# schematic-final.net
KiCad netlist of a schematic drawn in EAGLE
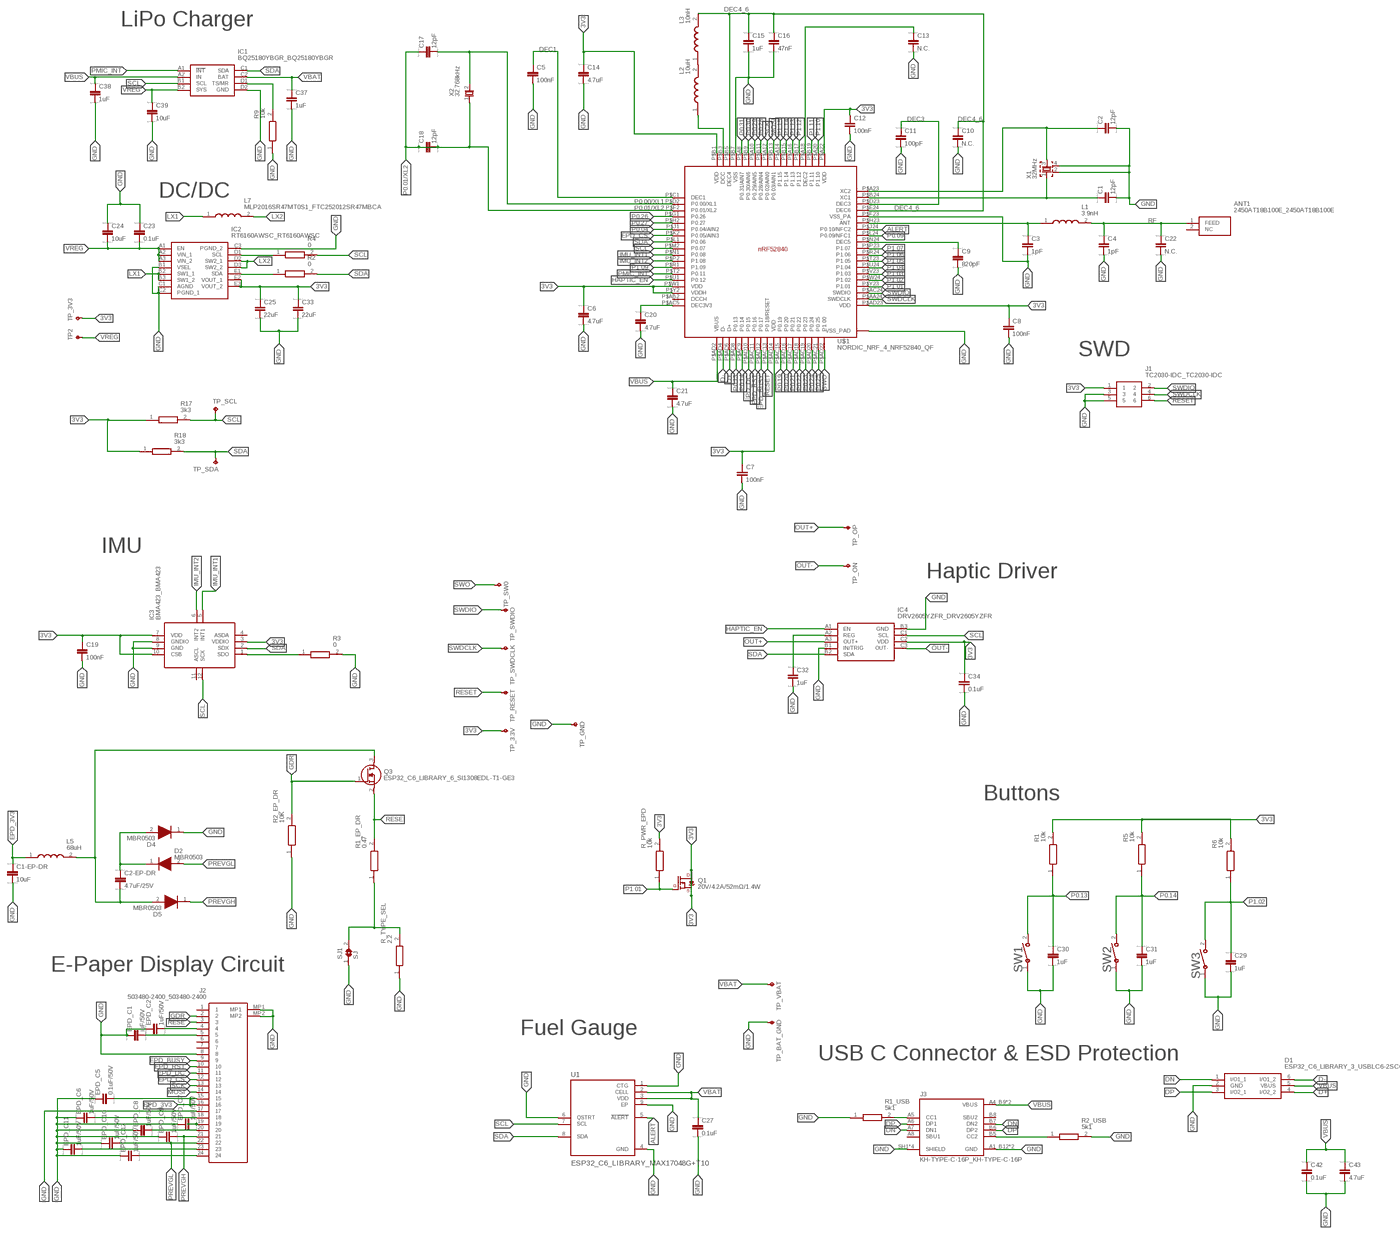
[diagram p0: schematic, sheet 1, overview]
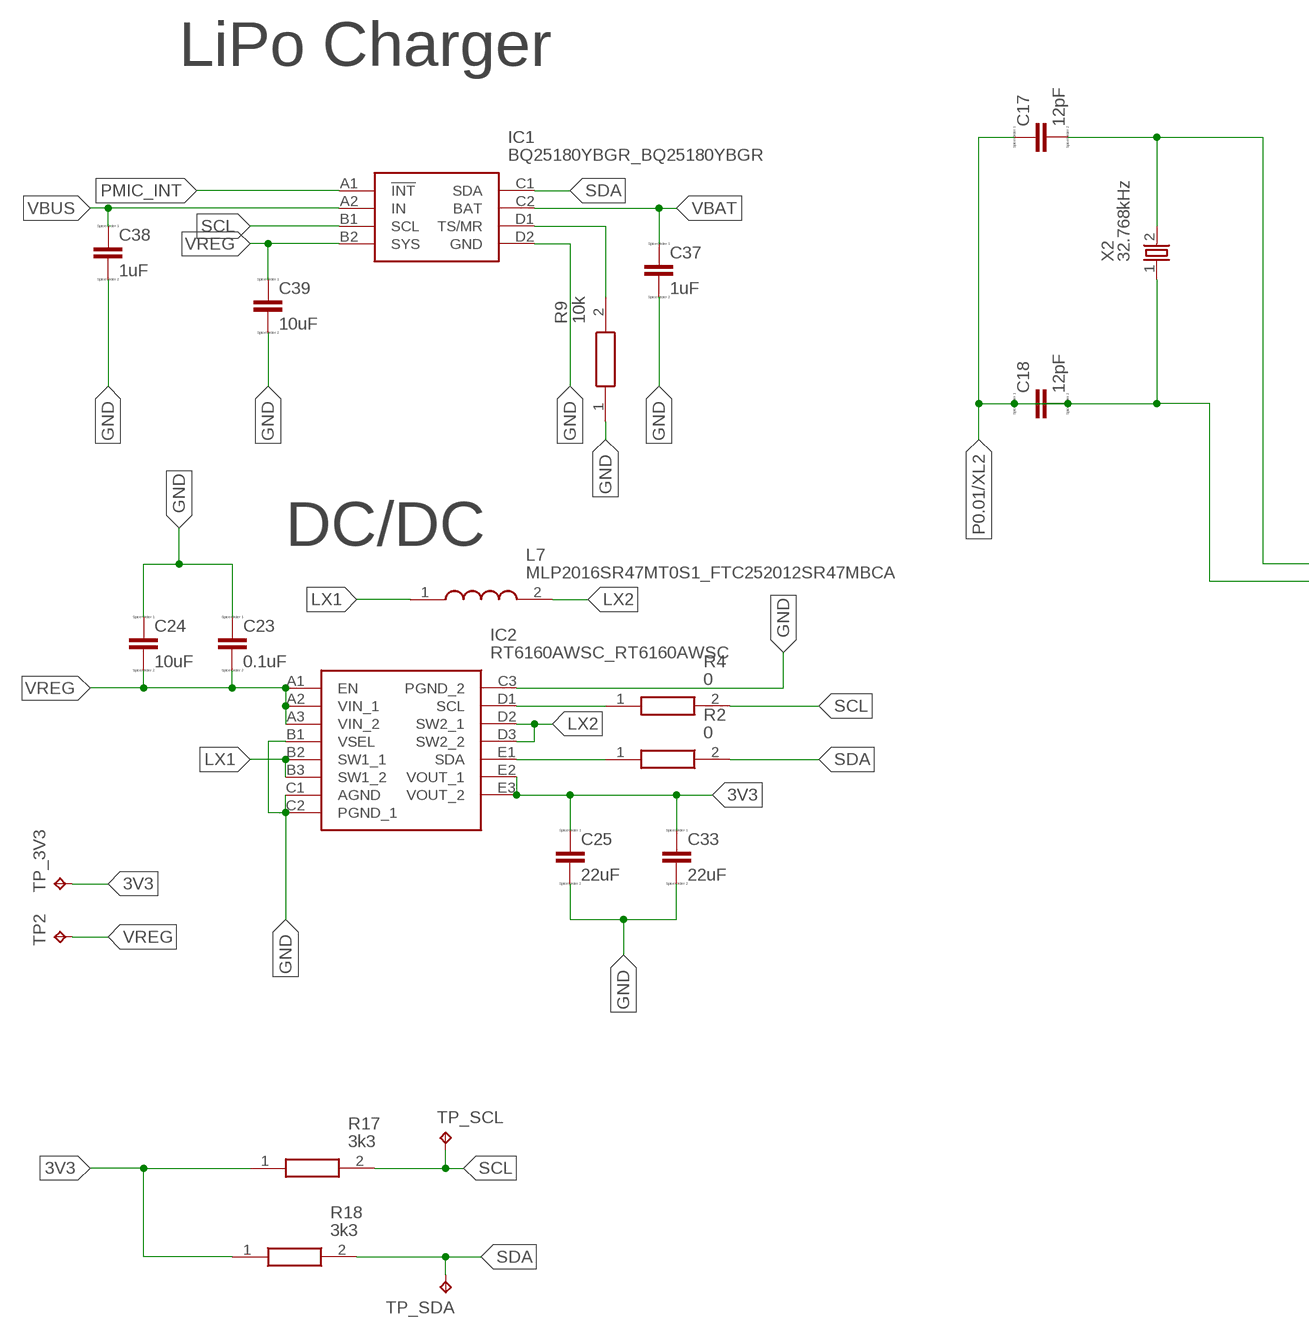
[diagram p1: schematic, sheet 1, part 1 of 4]
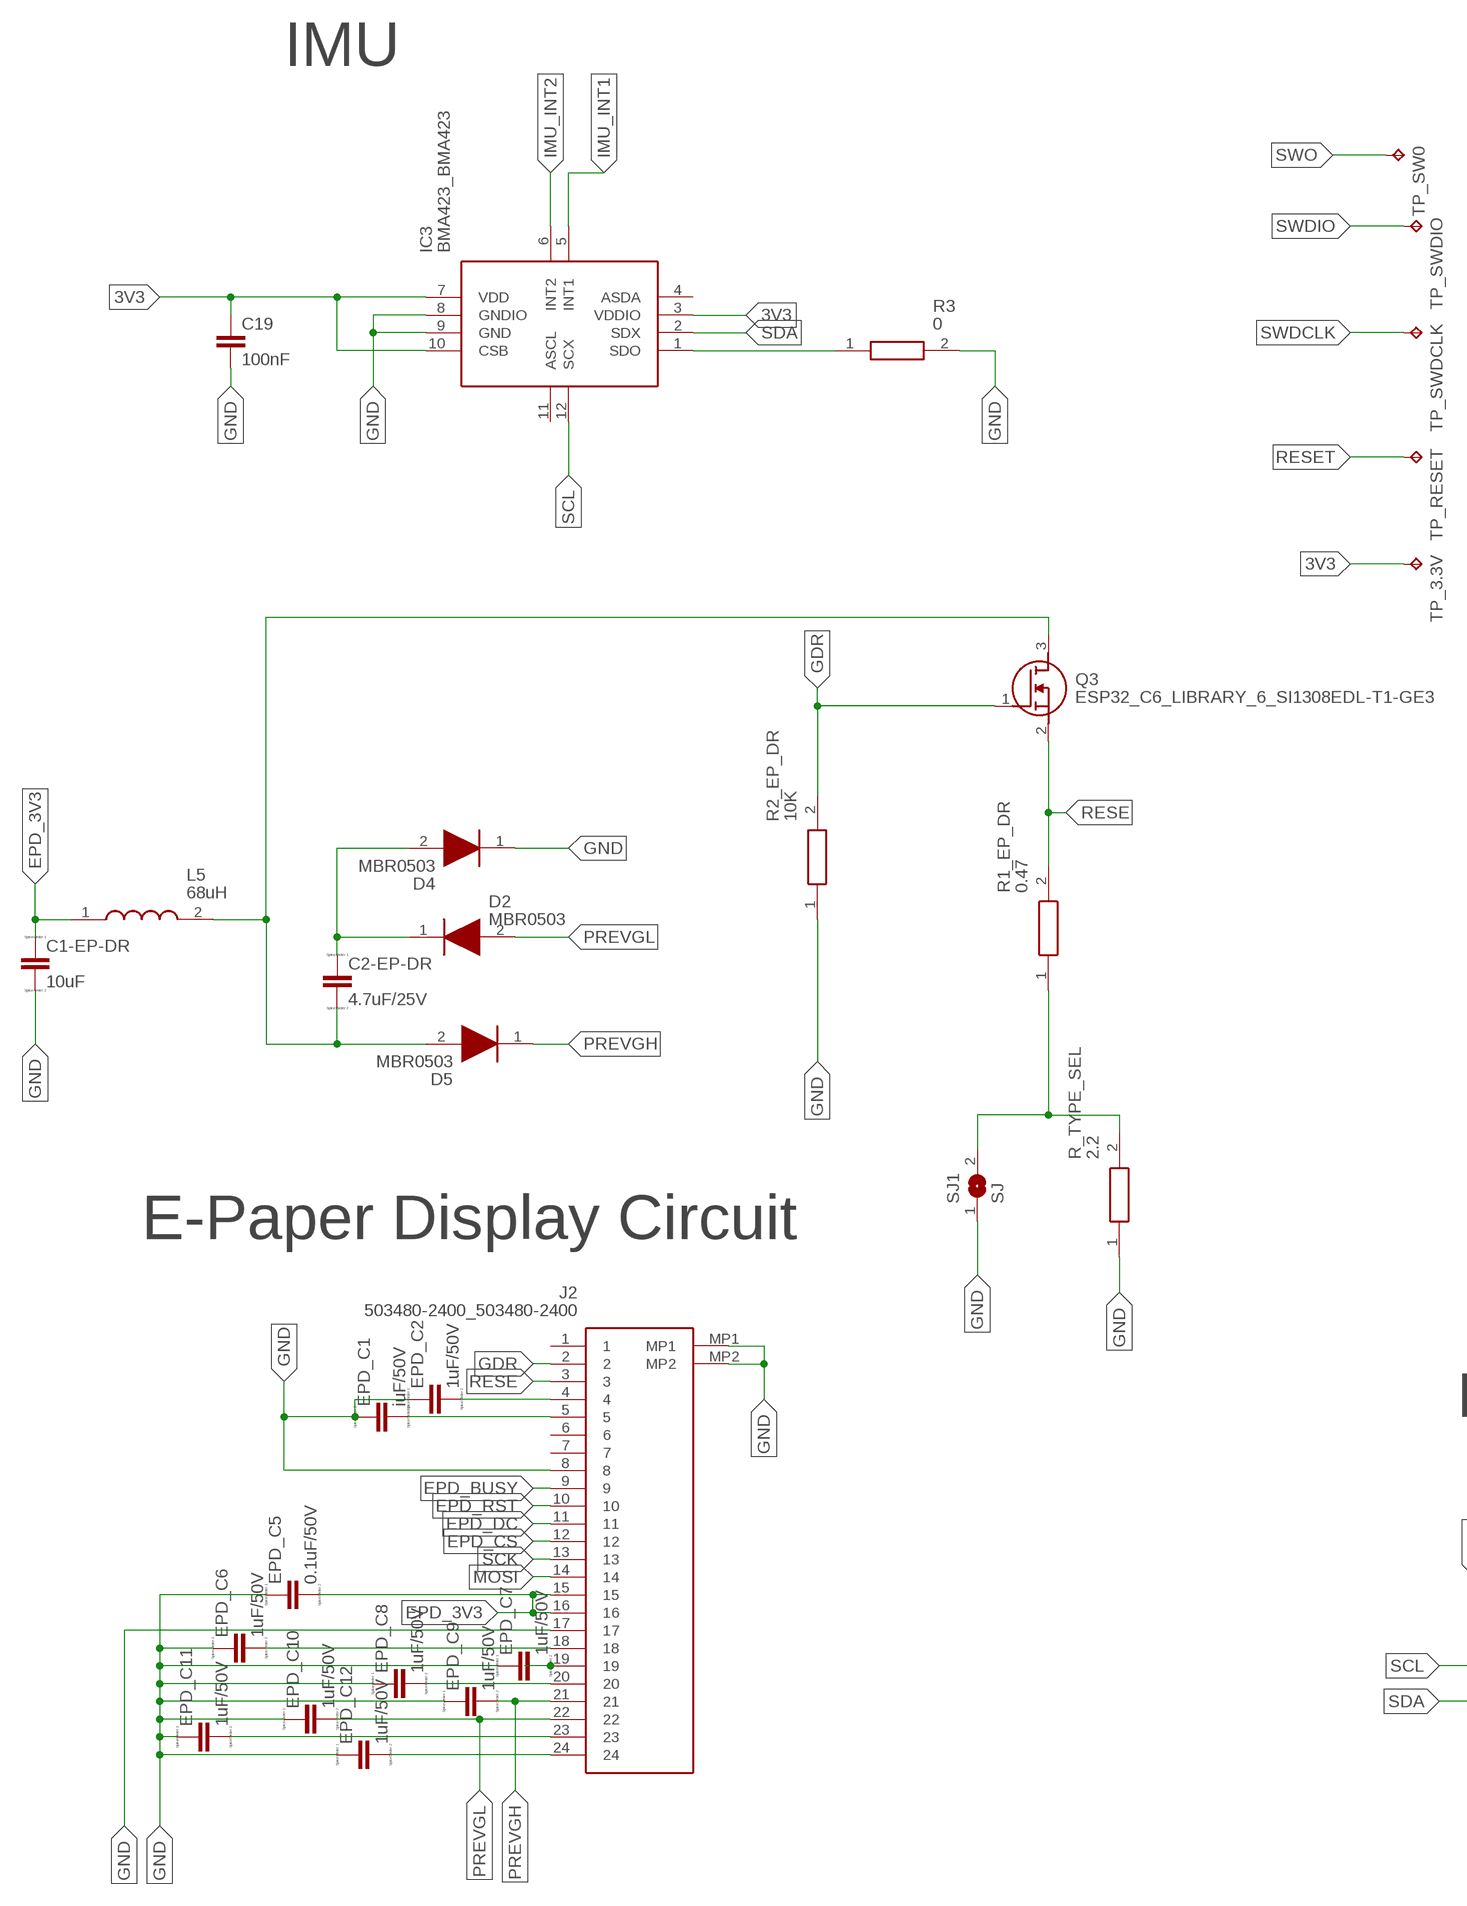
[diagram p2: schematic, sheet 1, part 2 of 4]
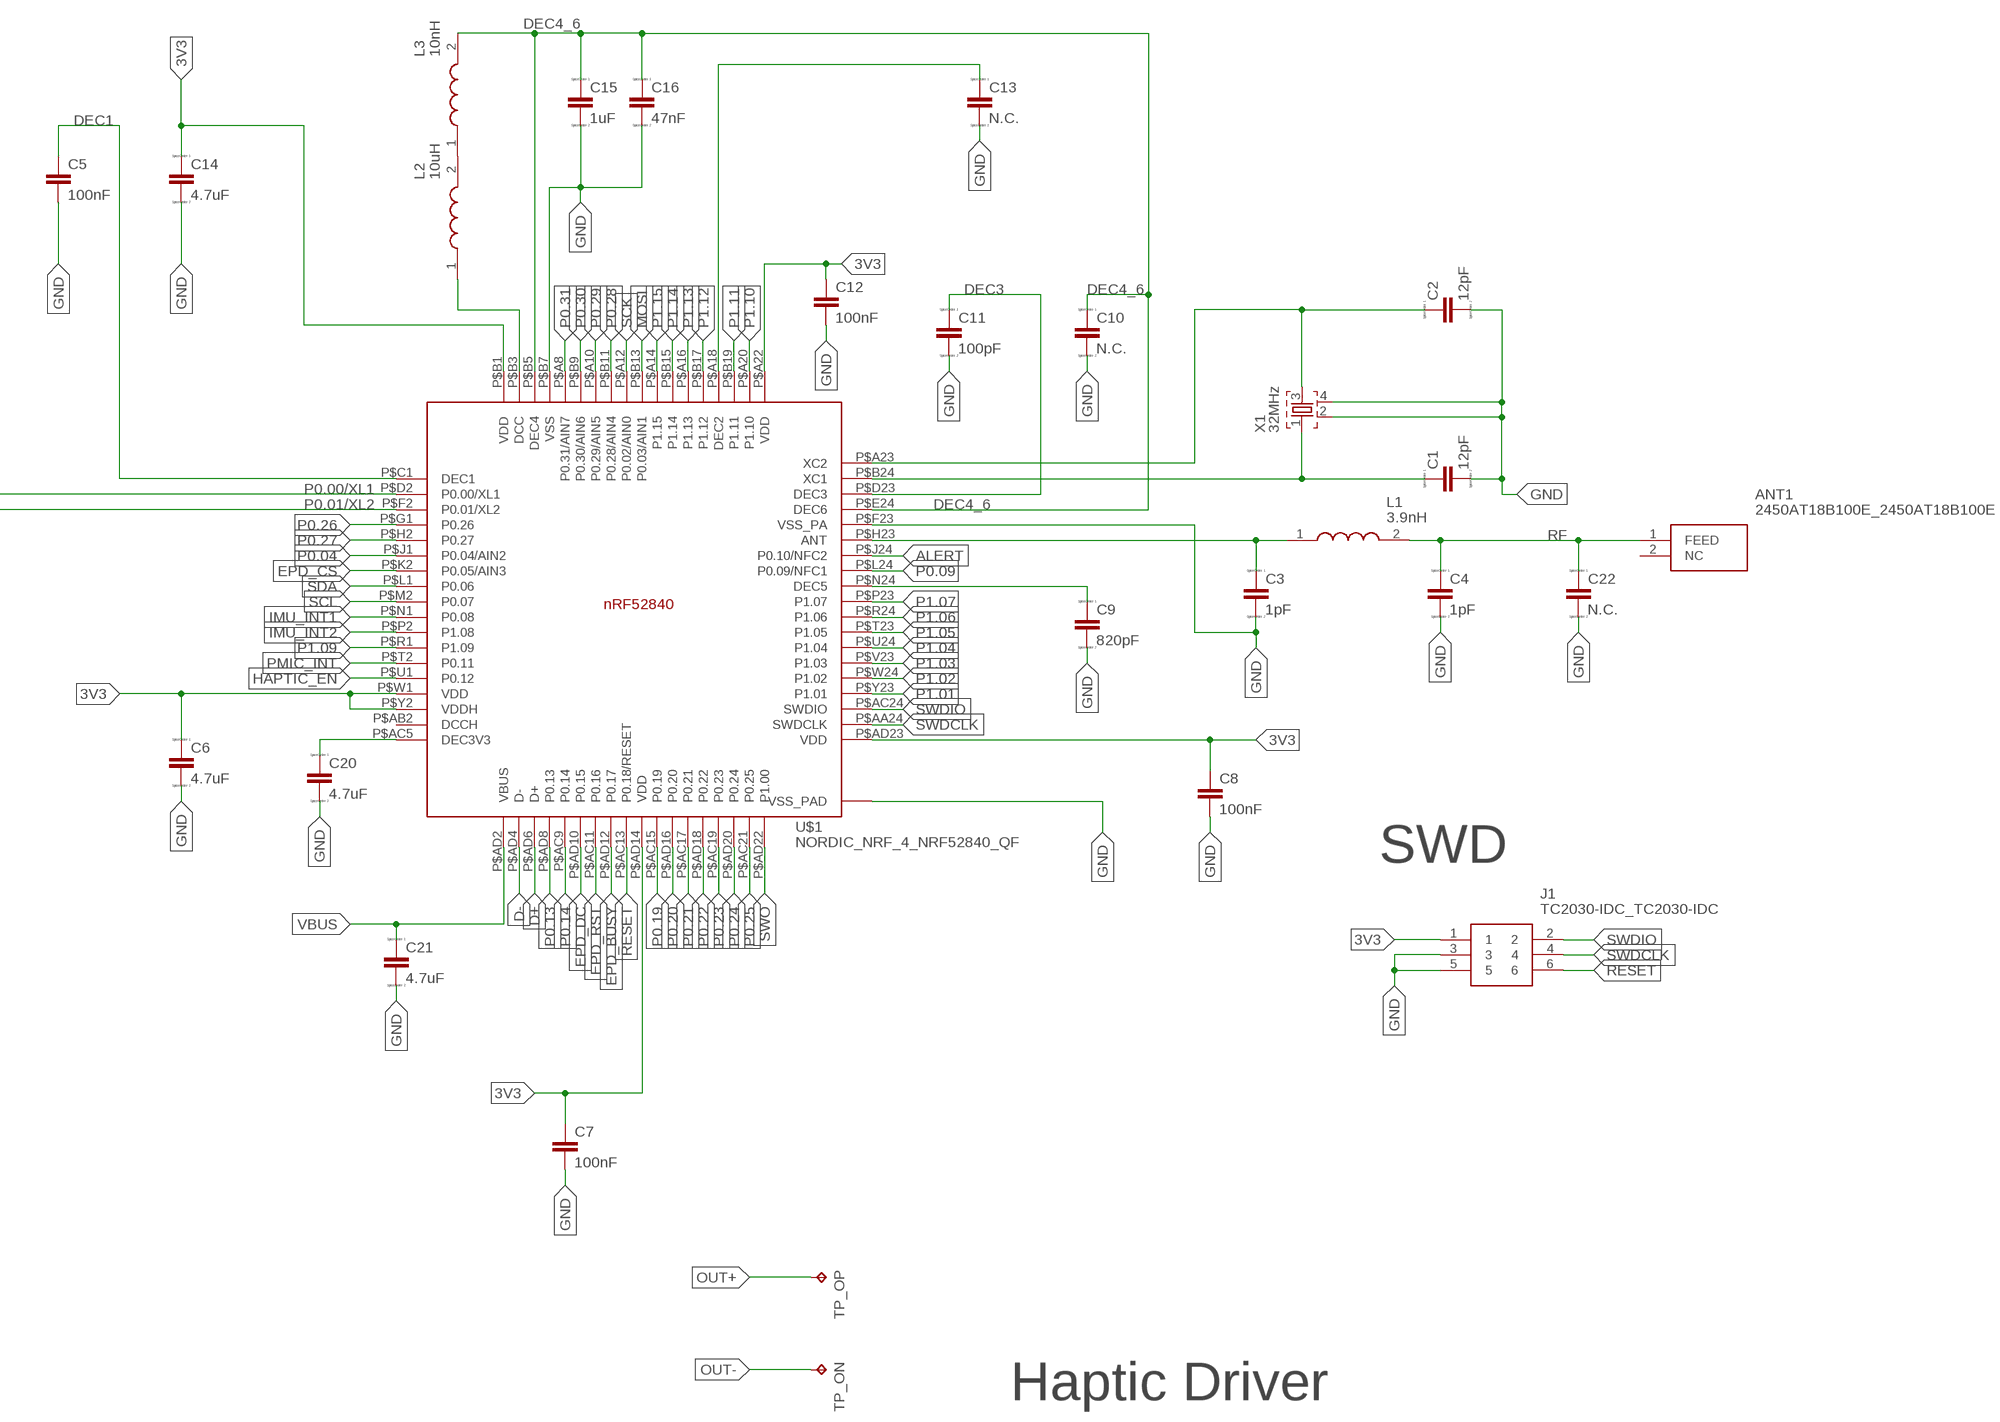
[diagram p3: schematic, sheet 1, part 3 of 4]
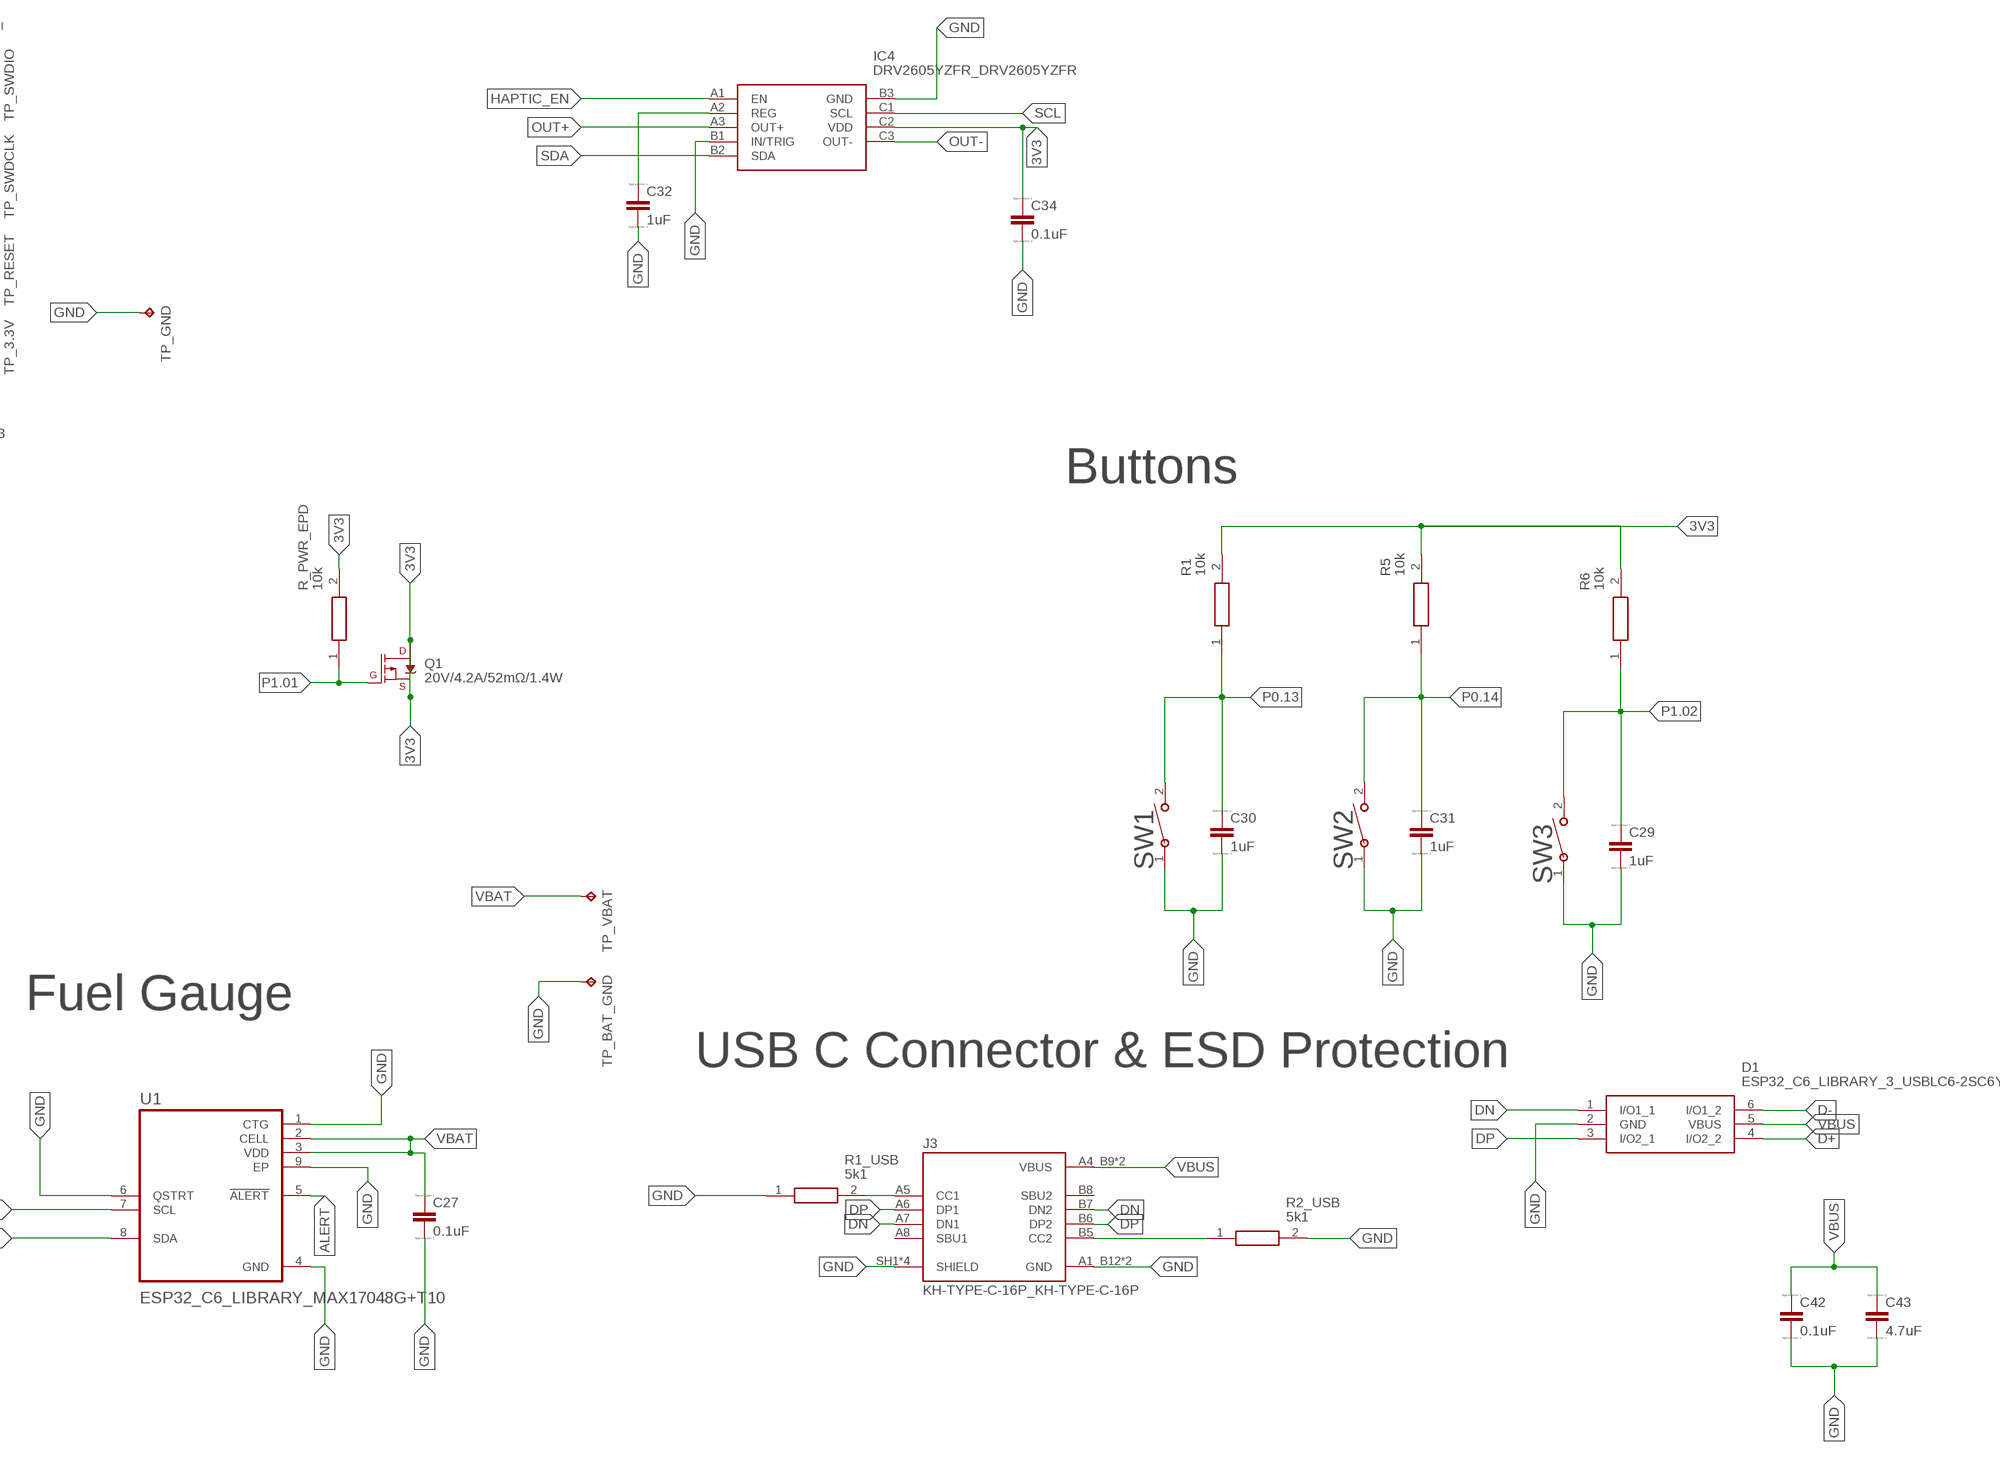
[diagram p4: schematic, sheet 1, part 4 of 4]

(export (version "E")
  (design (tool "Eeschema 10.0.6"))
  (components
    (comp (ref "ANT1")
      (value "2450AT18B100E_2450AT18B100E")
      (footprint "eagle-import:2450AT18B100E_ANTC3216X140N")
      (fields
        (field (name "ARROW_PART_NUMBER") "2450AT18B100E")
        (field (name "MOUSER_PART_NUMBER") "609-2450AT18B100E")
      )
      (libsource (lib "eagle-import") (part "2450AT18B100E_2450AT18B100E"))
    )
    (comp (ref "C1")
      (value "12pF")
      (footprint "eagle-import:ESP32_C6_LIBRARY_1_ESP32_WROVER_EAGLE-LTSPICE_C0402")
      (libsource (lib "eagle-import") (part "ESP32_C6_LIBRARY_1_ESP32_WROVER_EAGLE-LTSPICE_CC0402"))
    )
    (comp (ref "C1-EP-DR")
      (value "10uF")
      (footprint "eagle-import:ESP32_C6_LIBRARY_1_ESP32_WROVER_EAGLE-LTSPICE_C0402")
      (libsource (lib "eagle-import") (part "ESP32_C6_LIBRARY_1_ESP32_WROVER_EAGLE-LTSPICE_CC0402"))
    )
    (comp (ref "C2")
      (value "12pF")
      (footprint "eagle-import:ESP32_C6_LIBRARY_1_ESP32_WROVER_EAGLE-LTSPICE_C0402")
      (libsource (lib "eagle-import") (part "ESP32_C6_LIBRARY_1_ESP32_WROVER_EAGLE-LTSPICE_CC0402"))
    )
    (comp (ref "C2-EP-DR")
      (value "4.7uF/25V")
      (footprint "eagle-import:ESP32_C6_LIBRARY_1_ESP32_WROVER_EAGLE-LTSPICE_C0402")
      (libsource (lib "eagle-import") (part "ESP32_C6_LIBRARY_1_ESP32_WROVER_EAGLE-LTSPICE_CC0402"))
    )
    (comp (ref "C3")
      (value "1pF")
      (footprint "eagle-import:ESP32_C6_LIBRARY_1_ESP32_WROVER_EAGLE-LTSPICE_C0402")
      (libsource (lib "eagle-import") (part "ESP32_C6_LIBRARY_1_ESP32_WROVER_EAGLE-LTSPICE_CC0402"))
    )
    (comp (ref "C4")
      (value "1pF")
      (footprint "eagle-import:ESP32_C6_LIBRARY_1_ESP32_WROVER_EAGLE-LTSPICE_C0402")
      (libsource (lib "eagle-import") (part "ESP32_C6_LIBRARY_1_ESP32_WROVER_EAGLE-LTSPICE_CC0402"))
    )
    (comp (ref "C5")
      (value "100nF")
      (footprint "eagle-import:NORDIC_NRF_3_RESC0201_L")
      (libsource (lib "eagle-import") (part "NORDIC_NRF_3_CAPACITOR_0201_L"))
    )
    (comp (ref "C6")
      (value "4.7uF")
      (footprint "eagle-import:ESP32_C6_LIBRARY_1_ESP32_WROVER_EAGLE-LTSPICE_C0402")
      (libsource (lib "eagle-import") (part "ESP32_C6_LIBRARY_1_ESP32_WROVER_EAGLE-LTSPICE_CC0402"))
    )
    (comp (ref "C7")
      (value "100nF")
      (footprint "eagle-import:NORDIC_NRF_3_RESC0201_L")
      (libsource (lib "eagle-import") (part "NORDIC_NRF_3_CAPACITOR_0201_L"))
    )
    (comp (ref "C8")
      (value "100nF")
      (footprint "eagle-import:NORDIC_NRF_3_RESC0201_L")
      (libsource (lib "eagle-import") (part "NORDIC_NRF_3_CAPACITOR_0201_L"))
    )
    (comp (ref "C9")
      (value "820pF")
      (footprint "eagle-import:ESP32_C6_LIBRARY_1_ESP32_WROVER_EAGLE-LTSPICE_C0402")
      (libsource (lib "eagle-import") (part "ESP32_C6_LIBRARY_1_ESP32_WROVER_EAGLE-LTSPICE_CC0402"))
    )
    (comp (ref "C10")
      (value "N.C.")
      (footprint "eagle-import:ESP32_C6_LIBRARY_1_ESP32_WROVER_EAGLE-LTSPICE_C0402")
      (libsource (lib "eagle-import") (part "ESP32_C6_LIBRARY_1_ESP32_WROVER_EAGLE-LTSPICE_CC0402"))
    )
    (comp (ref "C11")
      (value "100pF")
      (footprint "eagle-import:ESP32_C6_LIBRARY_1_ESP32_WROVER_EAGLE-LTSPICE_C0402")
      (libsource (lib "eagle-import") (part "ESP32_C6_LIBRARY_1_ESP32_WROVER_EAGLE-LTSPICE_CC0402"))
    )
    (comp (ref "C12")
      (value "100nF")
      (footprint "eagle-import:NORDIC_NRF_3_RESC0201_L")
      (libsource (lib "eagle-import") (part "NORDIC_NRF_3_CAPACITOR_0201_L"))
    )
    (comp (ref "C13")
      (value "N.C.")
      (footprint "eagle-import:ESP32_C6_LIBRARY_1_ESP32_WROVER_EAGLE-LTSPICE_C0402")
      (libsource (lib "eagle-import") (part "ESP32_C6_LIBRARY_1_ESP32_WROVER_EAGLE-LTSPICE_CC0402"))
    )
    (comp (ref "C14")
      (value "4.7uF")
      (footprint "eagle-import:ESP32_C6_LIBRARY_1_ESP32_WROVER_EAGLE-LTSPICE_C0402")
      (libsource (lib "eagle-import") (part "ESP32_C6_LIBRARY_1_ESP32_WROVER_EAGLE-LTSPICE_CC0402"))
    )
    (comp (ref "C15")
      (value "1uF")
      (footprint "eagle-import:ESP32_C6_LIBRARY_1_ESP32_WROVER_EAGLE-LTSPICE_C0402")
      (libsource (lib "eagle-import") (part "ESP32_C6_LIBRARY_1_ESP32_WROVER_EAGLE-LTSPICE_CC0402"))
    )
    (comp (ref "C16")
      (value "47nF")
      (footprint "eagle-import:ESP32_C6_LIBRARY_1_ESP32_WROVER_EAGLE-LTSPICE_C0402")
      (libsource (lib "eagle-import") (part "ESP32_C6_LIBRARY_1_ESP32_WROVER_EAGLE-LTSPICE_CC0402"))
    )
    (comp (ref "C17")
      (value "12pF")
      (footprint "eagle-import:ESP32_C6_LIBRARY_1_ESP32_WROVER_EAGLE-LTSPICE_C0402")
      (libsource (lib "eagle-import") (part "ESP32_C6_LIBRARY_1_ESP32_WROVER_EAGLE-LTSPICE_CC0402"))
    )
    (comp (ref "C18")
      (value "12pF")
      (footprint "eagle-import:ESP32_C6_LIBRARY_1_ESP32_WROVER_EAGLE-LTSPICE_C0402")
      (libsource (lib "eagle-import") (part "ESP32_C6_LIBRARY_1_ESP32_WROVER_EAGLE-LTSPICE_CC0402"))
    )
    (comp (ref "C19")
      (value "100nF")
      (footprint "eagle-import:NORDIC_NRF_3_RESC0201_L")
      (libsource (lib "eagle-import") (part "NORDIC_NRF_3_CAPACITOR_0201_L"))
    )
    (comp (ref "C20")
      (value "4.7uF")
      (footprint "eagle-import:ESP32_C6_LIBRARY_1_ESP32_WROVER_EAGLE-LTSPICE_C0402")
      (libsource (lib "eagle-import") (part "ESP32_C6_LIBRARY_1_ESP32_WROVER_EAGLE-LTSPICE_CC0402"))
    )
    (comp (ref "C21")
      (value "4.7uF")
      (footprint "eagle-import:ESP32_C6_LIBRARY_1_ESP32_WROVER_EAGLE-LTSPICE_C0402")
      (libsource (lib "eagle-import") (part "ESP32_C6_LIBRARY_1_ESP32_WROVER_EAGLE-LTSPICE_CC0402"))
    )
    (comp (ref "C22")
      (value "N.C.")
      (footprint "eagle-import:ESP32_C6_LIBRARY_1_ESP32_WROVER_EAGLE-LTSPICE_C0402")
      (libsource (lib "eagle-import") (part "ESP32_C6_LIBRARY_1_ESP32_WROVER_EAGLE-LTSPICE_CC0402"))
    )
    (comp (ref "C23")
      (value "0.1uF")
      (footprint "eagle-import:ESP32_C6_LIBRARY_1_ESP32_WROVER_EAGLE-LTSPICE_C0402")
      (libsource (lib "eagle-import") (part "ESP32_C6_LIBRARY_1_ESP32_WROVER_EAGLE-LTSPICE_CC0402"))
    )
    (comp (ref "C24")
      (value "10uF")
      (footprint "eagle-import:ESP32_C6_LIBRARY_1_ESP32_WROVER_EAGLE-LTSPICE_C0402")
      (libsource (lib "eagle-import") (part "ESP32_C6_LIBRARY_1_ESP32_WROVER_EAGLE-LTSPICE_CC0402"))
    )
    (comp (ref "C25")
      (value "22uF")
      (footprint "eagle-import:ESP32_C6_LIBRARY_1_ESP32_WROVER_EAGLE-LTSPICE_C0402")
      (libsource (lib "eagle-import") (part "ESP32_C6_LIBRARY_1_ESP32_WROVER_EAGLE-LTSPICE_CC0402"))
    )
    (comp (ref "C27")
      (value "0.1uF")
      (footprint "eagle-import:ESP32_C6_LIBRARY_1_ESP32_WROVER_EAGLE-LTSPICE_C0402")
      (libsource (lib "eagle-import") (part "ESP32_C6_LIBRARY_1_ESP32_WROVER_EAGLE-LTSPICE_CC0402"))
    )
    (comp (ref "C29")
      (value "1uF")
      (footprint "eagle-import:ESP32_C6_LIBRARY_1_ESP32_WROVER_EAGLE-LTSPICE_C0402")
      (libsource (lib "eagle-import") (part "ESP32_C6_LIBRARY_1_ESP32_WROVER_EAGLE-LTSPICE_CC0402"))
    )
    (comp (ref "C30")
      (value "1uF")
      (footprint "eagle-import:ESP32_C6_LIBRARY_1_ESP32_WROVER_EAGLE-LTSPICE_C0402")
      (libsource (lib "eagle-import") (part "ESP32_C6_LIBRARY_1_ESP32_WROVER_EAGLE-LTSPICE_CC0402"))
    )
    (comp (ref "C31")
      (value "1uF")
      (footprint "eagle-import:ESP32_C6_LIBRARY_1_ESP32_WROVER_EAGLE-LTSPICE_C0402")
      (libsource (lib "eagle-import") (part "ESP32_C6_LIBRARY_1_ESP32_WROVER_EAGLE-LTSPICE_CC0402"))
    )
    (comp (ref "C32")
      (value "1uF")
      (footprint "eagle-import:ESP32_C6_LIBRARY_1_ESP32_WROVER_EAGLE-LTSPICE_C0402")
      (libsource (lib "eagle-import") (part "ESP32_C6_LIBRARY_1_ESP32_WROVER_EAGLE-LTSPICE_CC0402"))
    )
    (comp (ref "C33")
      (value "22uF")
      (footprint "eagle-import:ESP32_C6_LIBRARY_1_ESP32_WROVER_EAGLE-LTSPICE_C0402")
      (libsource (lib "eagle-import") (part "ESP32_C6_LIBRARY_1_ESP32_WROVER_EAGLE-LTSPICE_CC0402"))
    )
    (comp (ref "C34")
      (value "0.1uF")
      (footprint "eagle-import:ESP32_C6_LIBRARY_1_ESP32_WROVER_EAGLE-LTSPICE_C0402")
      (libsource (lib "eagle-import") (part "ESP32_C6_LIBRARY_1_ESP32_WROVER_EAGLE-LTSPICE_CC0402"))
    )
    (comp (ref "C37")
      (value "1uF")
      (footprint "eagle-import:ESP32_C6_LIBRARY_1_ESP32_WROVER_EAGLE-LTSPICE_C0402")
      (libsource (lib "eagle-import") (part "ESP32_C6_LIBRARY_1_ESP32_WROVER_EAGLE-LTSPICE_CC0402"))
    )
    (comp (ref "C38")
      (value "1uF")
      (footprint "eagle-import:ESP32_C6_LIBRARY_1_ESP32_WROVER_EAGLE-LTSPICE_C0402")
      (libsource (lib "eagle-import") (part "ESP32_C6_LIBRARY_1_ESP32_WROVER_EAGLE-LTSPICE_CC0402"))
    )
    (comp (ref "C39")
      (value "10uF")
      (footprint "eagle-import:ESP32_C6_LIBRARY_1_ESP32_WROVER_EAGLE-LTSPICE_C0402")
      (libsource (lib "eagle-import") (part "ESP32_C6_LIBRARY_1_ESP32_WROVER_EAGLE-LTSPICE_CC0402"))
    )
    (comp (ref "C42")
      (value "0.1uF")
      (footprint "eagle-import:ESP32_C6_LIBRARY_1_ESP32_WROVER_EAGLE-LTSPICE_C0402")
      (libsource (lib "eagle-import") (part "ESP32_C6_LIBRARY_1_ESP32_WROVER_EAGLE-LTSPICE_CC0402"))
    )
    (comp (ref "C43")
      (value "4.7uF")
      (footprint "eagle-import:ESP32_C6_LIBRARY_1_ESP32_WROVER_EAGLE-LTSPICE_C0402")
      (libsource (lib "eagle-import") (part "ESP32_C6_LIBRARY_1_ESP32_WROVER_EAGLE-LTSPICE_CC0402"))
    )
    (comp (ref "D1")
      (value "ESP32_C6_LIBRARY_3_USBLC6-2SC6Y")
      (footprint "eagle-import:ESP32_C6_LIBRARY_3_SOT95P280X145-6N")
      (fields (field (name "MF") "STMicroelectronics") (field (name "MP") "USBLC6-2SC6Y"))
      (libsource (lib "eagle-import") (part "ESP32_C6_LIBRARY_3_USBLC6-2SC6Y"))
    )
    (comp (ref "D2")
      (value "MBR0503")
      (footprint "eagle-import:ESP32_C6_LIBRARY_5_SOD3716X135N")
      (fields (field (name "MF") "ON Semiconductor") (field (name "MP") "MBR0530"))
      (libsource (lib "eagle-import") (part "ESP32_C6_LIBRARY_5_MBR0530"))
    )
    (comp (ref "D4")
      (value "MBR0503")
      (footprint "eagle-import:ESP32_C6_LIBRARY_5_SOD3716X135N")
      (fields (field (name "MF") "ON Semiconductor") (field (name "MP") "MBR0530"))
      (libsource (lib "eagle-import") (part "ESP32_C6_LIBRARY_5_MBR0530"))
    )
    (comp (ref "D5")
      (value "MBR0503")
      (footprint "eagle-import:ESP32_C6_LIBRARY_5_SOD3716X135N")
      (fields (field (name "MF") "ON Semiconductor") (field (name "MP") "MBR0530"))
      (libsource (lib "eagle-import") (part "ESP32_C6_LIBRARY_5_MBR0530"))
    )
    (comp (ref "EPD_C1")
      (value "iuF/50V")
      (footprint "eagle-import:ESP32_C6_LIBRARY_1_ESP32_WROVER_EAGLE-LTSPICE_C0402")
      (libsource (lib "eagle-import") (part "ESP32_C6_LIBRARY_1_ESP32_WROVER_EAGLE-LTSPICE_CC0402"))
    )
    (comp (ref "EPD_C2")
      (value "1uF/50V")
      (footprint "eagle-import:ESP32_C6_LIBRARY_1_ESP32_WROVER_EAGLE-LTSPICE_C0402")
      (libsource (lib "eagle-import") (part "ESP32_C6_LIBRARY_1_ESP32_WROVER_EAGLE-LTSPICE_CC0402"))
    )
    (comp (ref "EPD_C5")
      (value "0.1uF/50V")
      (footprint "eagle-import:ESP32_C6_LIBRARY_1_ESP32_WROVER_EAGLE-LTSPICE_C0402")
      (libsource (lib "eagle-import") (part "ESP32_C6_LIBRARY_1_ESP32_WROVER_EAGLE-LTSPICE_CC0402"))
    )
    (comp (ref "EPD_C6")
      (value "1uF/50V")
      (footprint "eagle-import:ESP32_C6_LIBRARY_1_ESP32_WROVER_EAGLE-LTSPICE_C0402")
      (libsource (lib "eagle-import") (part "ESP32_C6_LIBRARY_1_ESP32_WROVER_EAGLE-LTSPICE_CC0402"))
    )
    (comp (ref "EPD_C7")
      (value "1uF/50V")
      (footprint "eagle-import:ESP32_C6_LIBRARY_1_ESP32_WROVER_EAGLE-LTSPICE_C0402")
      (libsource (lib "eagle-import") (part "ESP32_C6_LIBRARY_1_ESP32_WROVER_EAGLE-LTSPICE_CC0402"))
    )
    (comp (ref "EPD_C8")
      (value "1uF/50V")
      (footprint "eagle-import:ESP32_C6_LIBRARY_1_ESP32_WROVER_EAGLE-LTSPICE_C0402")
      (libsource (lib "eagle-import") (part "ESP32_C6_LIBRARY_1_ESP32_WROVER_EAGLE-LTSPICE_CC0402"))
    )
    (comp (ref "EPD_C9")
      (value "1uF/50V")
      (footprint "eagle-import:ESP32_C6_LIBRARY_1_ESP32_WROVER_EAGLE-LTSPICE_C0402")
      (libsource (lib "eagle-import") (part "ESP32_C6_LIBRARY_1_ESP32_WROVER_EAGLE-LTSPICE_CC0402"))
    )
    (comp (ref "EPD_C10")
      (value "1uF/50V")
      (footprint "eagle-import:ESP32_C6_LIBRARY_1_ESP32_WROVER_EAGLE-LTSPICE_C0402")
      (libsource (lib "eagle-import") (part "ESP32_C6_LIBRARY_1_ESP32_WROVER_EAGLE-LTSPICE_CC0402"))
    )
    (comp (ref "EPD_C11")
      (value "1uF/50V")
      (footprint "eagle-import:ESP32_C6_LIBRARY_1_ESP32_WROVER_EAGLE-LTSPICE_C0402")
      (libsource (lib "eagle-import") (part "ESP32_C6_LIBRARY_1_ESP32_WROVER_EAGLE-LTSPICE_CC0402"))
    )
    (comp (ref "EPD_C12")
      (value "1uF/50V")
      (footprint "eagle-import:ESP32_C6_LIBRARY_1_ESP32_WROVER_EAGLE-LTSPICE_C0402")
      (libsource (lib "eagle-import") (part "ESP32_C6_LIBRARY_1_ESP32_WROVER_EAGLE-LTSPICE_CC0402"))
    )
    (comp (ref "IC1")
      (value "BQ25180YBGR_BQ25180YBGR")
      (footprint "eagle-import:BQ25180YBGR_BGA8C40P2X4_100X155X50")
      (fields
        (field (name "ARROW_PART_NUMBER") "BQ25180YBGR")
        (field (name "MOUSER_PART_NUMBER") "595-BQ25180YBGR")
      )
      (libsource (lib "eagle-import") (part "BQ25180YBGR_BQ25180YBGR"))
    )
    (comp (ref "IC2")
      (value "RT6160AWSC_RT6160AWSC")
      (footprint "eagle-import:RT6160AWSC_BGA15C40P3X5_140X230X60")
      (fields
        (field (name "MANUFACTURER_PART_NUMBER") "RT6160AWSC")
        (field (name "MOUSER_PART_NUMBER") "835-RT6160AWSC")
      )
      (libsource (lib "eagle-import") (part "RT6160AWSC_RT6160AWSC"))
    )
    (comp (ref "IC3")
      (value "BMA423_BMA423")
      (footprint "eagle-import:BMA423_BMA423")
      (fields (field (name "ARROW_PART_NUMBER") "BMA423") (field (name "MOUSER_PART_NUMBER") "262-BMA423"))
      (libsource (lib "eagle-import") (part "BMA423_BMA423"))
    )
    (comp (ref "IC4")
      (value "DRV2605YZFR_DRV2605YZFR")
      (footprint "eagle-import:DRV2605YZFR_BGA9C50P3X3_144X144X62")
      (fields (field (name "ARROW_PART_NUMBER") "DRV2605YZFR"))
      (libsource (lib "eagle-import") (part "DRV2605YZFR_DRV2605YZFR"))
    )
    (comp (ref "J1")
      (value "TC2030-IDC_TC2030-IDC")
      (footprint "eagle-import:TC2030-IDC_TC2030IDC")
      (fields (field (name "MANUFACTURER_PART_NUMBER") "TC2030-IDC"))
      (libsource (lib "eagle-import") (part "TC2030-IDC_TC2030-IDC"))
    )
    (comp (ref "J2")
      (value "503480-2400_503480-2400")
      (footprint "eagle-import:503480-2400_5034802400")
      (fields
        (field (name "MANUFACTURER_PART_NUMBER") "503480-2400")
        (field (name "MOUSER_PART_NUMBER") "538-503480-2400")
      )
      (libsource (lib "eagle-import") (part "503480-2400_503480-2400"))
    )
    (comp (ref "J3")
      (value "KH-TYPE-C-16P_KH-TYPE-C-16P")
      (footprint "eagle-import:KH-TYPE-C-16P_KINGHELM_KH-TYPE-C-16P")
      (fields (field (name "MF") "kinghelm") (field (name "MP") "KH-TYPE-C-16P"))
      (libsource (lib "eagle-import") (part "KH-TYPE-C-16P_KH-TYPE-C-16P"))
    )
    (comp (ref "L1")
      (value "3.9nH")
      (footprint "eagle-import:MLP2016SR47MT0S1_INDC2016X100N")
      (fields (field (name "MANUFACTURER_PART_NUMBER") "FTC252012SR47MBCA"))
      (libsource (lib "eagle-import") (part "MLP2016SR47MT0S1_FTC252012SR47MBCA"))
    )
    (comp (ref "L2")
      (value "10uH")
      (footprint "eagle-import:MLP2016SR47MT0S1_INDC2016X100N")
      (fields (field (name "MANUFACTURER_PART_NUMBER") "FTC252012SR47MBCA"))
      (libsource (lib "eagle-import") (part "MLP2016SR47MT0S1_FTC252012SR47MBCA"))
    )
    (comp (ref "L3")
      (value "10nH")
      (footprint "eagle-import:MLP2016SR47MT0S1_INDC2016X100N")
      (fields (field (name "MANUFACTURER_PART_NUMBER") "FTC252012SR47MBCA"))
      (libsource (lib "eagle-import") (part "MLP2016SR47MT0S1_FTC252012SR47MBCA"))
    )
    (comp (ref "L5")
      (value "68uH")
      (footprint "eagle-import:MLP2016SR47MT0S1_INDC2016X100N")
      (fields (field (name "MANUFACTURER_PART_NUMBER") "FTC252012SR47MBCA"))
      (libsource (lib "eagle-import") (part "MLP2016SR47MT0S1_FTC252012SR47MBCA"))
    )
    (comp (ref "L7")
      (value "MLP2016SR47MT0S1_FTC252012SR47MBCA")
      (footprint "eagle-import:MLP2016SR47MT0S1_INDC2016X100N")
      (fields (field (name "MANUFACTURER_PART_NUMBER") "FTC252012SR47MBCA"))
      (libsource (lib "eagle-import") (part "MLP2016SR47MT0S1_FTC252012SR47MBCA"))
    )
    (comp (ref "Q1")
      (value "20V/4.2A/52mΩ/1.4W")
      (footprint "eagle-import:ESP32_C6_LIBRARY_4_ESP32_C6_LIBRARY_4_ESP32_C6_LIBRARY_4_ESP32_C6_LIBRARY_4_ESP32_WROVER_SPARKFUN-DISCRETESEMI_SOT23-3")
      (libsource (lib "eagle-import") (part "ESP32_C6_LIBRARY_4_ESP32_WROVER_SPARKFUN-DISCRETESEMI_MOSFET_PCH-DMG2305UX-7"))
    )
    (comp (ref "Q3")
      (value "ESP32_C6_LIBRARY_6_SI1308EDL-T1-GE3")
      (footprint "eagle-import:ESP32_C6_LIBRARY_6_SOT65P210X110-3N")
      (fields (field (name "MF") "Vishay Siliconix") (field (name "MP") "SI1308EDL-T1-GE3"))
      (libsource (lib "eagle-import") (part "ESP32_C6_LIBRARY_6_SI1308EDL-T1-GE3"))
    )
    (comp (ref "R1")
      (value "10k")
      (footprint "eagle-import:ERA-1AEB3401C_0201")
      (libsource (lib "eagle-import") (part "ERA-1AEB3401C_CPF0201D7K68C1"))
    )
    (comp (ref "R1_EP_DR")
      (value "0.47")
      (footprint "eagle-import:ERA-1AEB3401C_0201")
      (libsource (lib "eagle-import") (part "ERA-1AEB3401C_CPF0201D7K68C1"))
    )
    (comp (ref "R1_USB")
      (value "5k1")
      (footprint "eagle-import:ERA-1AEB3401C_0201")
      (libsource (lib "eagle-import") (part "ERA-1AEB3401C_CPF0201D7K68C1"))
    )
    (comp (ref "R2")
      (value "0")
      (footprint "eagle-import:ERA-1AEB3401C_0201")
      (libsource (lib "eagle-import") (part "ERA-1AEB3401C_CPF0201D7K68C1"))
    )
    (comp (ref "R2_EP_DR")
      (value "10K")
      (footprint "eagle-import:ERA-1AEB3401C_0201")
      (libsource (lib "eagle-import") (part "ERA-1AEB3401C_CPF0201D7K68C1"))
    )
    (comp (ref "R2_USB")
      (value "5k1")
      (footprint "eagle-import:ERA-1AEB3401C_0201")
      (libsource (lib "eagle-import") (part "ERA-1AEB3401C_CPF0201D7K68C1"))
    )
    (comp (ref "R3")
      (value "0")
      (footprint "eagle-import:ERA-1AEB3401C_0201")
      (libsource (lib "eagle-import") (part "ERA-1AEB3401C_CPF0201D7K68C1"))
    )
    (comp (ref "R4")
      (value "0")
      (footprint "eagle-import:ERA-1AEB3401C_0201")
      (libsource (lib "eagle-import") (part "ERA-1AEB3401C_CPF0201D7K68C1"))
    )
    (comp (ref "R5")
      (value "10k")
      (footprint "eagle-import:ERA-1AEB3401C_0201")
      (libsource (lib "eagle-import") (part "ERA-1AEB3401C_CPF0201D7K68C1"))
    )
    (comp (ref "R6")
      (value "10k")
      (footprint "eagle-import:ERA-1AEB3401C_0201")
      (libsource (lib "eagle-import") (part "ERA-1AEB3401C_CPF0201D7K68C1"))
    )
    (comp (ref "R9")
      (value "10k")
      (footprint "eagle-import:CPF0201D7K68C1_0201")
      (libsource (lib "eagle-import") (part "CPF0201D7K68C1_CPF0201D7K68C1"))
    )
    (comp (ref "R17")
      (value "3k3")
      (footprint "eagle-import:ERA-1AEB3401C_0201")
      (libsource (lib "eagle-import") (part "ERA-1AEB3401C_CPF0201D7K68C1"))
    )
    (comp (ref "R18")
      (value "3k3")
      (footprint "eagle-import:ERA-1AEB3401C_0201")
      (libsource (lib "eagle-import") (part "ERA-1AEB3401C_CPF0201D7K68C1"))
    )
    (comp (ref "R_PWR_EPD")
      (value "10k")
      (footprint "eagle-import:ERA-1AEB3401C_0201")
      (libsource (lib "eagle-import") (part "ERA-1AEB3401C_CPF0201D7K68C1"))
    )
    (comp (ref "R_TYPE_SEL")
      (value "2.2")
      (footprint "eagle-import:ERA-1AEB3401C_0201")
      (libsource (lib "eagle-import") (part "ERA-1AEB3401C_CPF0201D7K68C1"))
    )
    (comp (ref "SJ1")
      (value "SJ")
      (footprint "eagle-import:ESP32_C6_LIBRARY_7_JUMPER_SJ")
      (libsource (lib "eagle-import") (part "ESP32_C6_LIBRARY_7_JUMPER_SJ"))
    )
    (comp (ref "SW1")
      (value "2025-10-22_07-23-44_LIBRARY_EVP-AKE31ASW_EVP-AKE31A_PAN")
      (footprint "eagle-import:2025-10-22_07-23-44_LIBRARY_SW_EVP-AKE31A_PAN")
      (fields
        (field (name "MANUFACTURER_PART_NUMBER") "EVP-AKE31A")
        (field (name "COPYRIGHT") "Copyright (C) 2025 Ultra Librarian. All rights reserved.")
      )
      (libsource (lib "eagle-import") (part "2025-10-22_07-23-44_LIBRARY_EVP-AKE31ASW_EVP-AKE31A_PAN"))
    )
    (comp (ref "SW2")
      (value "2025-10-22_07-23-44_LIBRARY_EVP-AKE31ASW_EVP-AKE31A_PAN")
      (footprint "eagle-import:2025-10-22_07-23-44_LIBRARY_SW_EVP-AKE31A_PAN")
      (fields
        (field (name "MANUFACTURER_PART_NUMBER") "EVP-AKE31A")
        (field (name "COPYRIGHT") "Copyright (C) 2025 Ultra Librarian. All rights reserved.")
      )
      (libsource (lib "eagle-import") (part "2025-10-22_07-23-44_LIBRARY_EVP-AKE31ASW_EVP-AKE31A_PAN"))
    )
    (comp (ref "SW3")
      (value "2025-10-22_07-23-44_LIBRARY_EVP-AKE31ASW_EVP-AKE31A_PAN")
      (footprint "eagle-import:2025-10-22_07-23-44_LIBRARY_SW_EVP-AKE31A_PAN")
      (fields
        (field (name "MANUFACTURER_PART_NUMBER") "EVP-AKE31A")
        (field (name "COPYRIGHT") "Copyright (C) 2025 Ultra Librarian. All rights reserved.")
      )
      (libsource (lib "eagle-import") (part "2025-10-22_07-23-44_LIBRARY_EVP-AKE31ASW_EVP-AKE31A_PAN"))
    )
    (comp (ref "TP2")
      (value "HECTOR_WATCH_1_TPTP20R")
      (footprint "eagle-import:HECTOR_WATCH_1_TP20R")
      (libsource (lib "eagle-import") (part "HECTOR_WATCH_1_TPTP20R"))
    )
    (comp (ref "TP_3.3V")
      (value "HECTOR_WATCH_1_TPTP20R")
      (footprint "eagle-import:HECTOR_WATCH_1_TP20R")
      (libsource (lib "eagle-import") (part "HECTOR_WATCH_1_TPTP20R"))
    )
    (comp (ref "TP_3V3")
      (value "HECTOR_WATCH_1_TPTP20R")
      (footprint "eagle-import:HECTOR_WATCH_1_TP20R")
      (libsource (lib "eagle-import") (part "HECTOR_WATCH_1_TPTP20R"))
    )
    (comp (ref "TP_BAT_GND")
      (value "HECTOR_WATCH_1_TPTP20R")
      (footprint "eagle-import:HECTOR_WATCH_1_TP20R")
      (libsource (lib "eagle-import") (part "HECTOR_WATCH_1_TPTP20R"))
    )
    (comp (ref "TP_GND")
      (value "HECTOR_WATCH_1_TPTP20R")
      (footprint "eagle-import:HECTOR_WATCH_1_TP20R")
      (libsource (lib "eagle-import") (part "HECTOR_WATCH_1_TPTP20R"))
    )
    (comp (ref "TP_ON")
      (value "HECTOR_WATCH_1_TPTP20R")
      (footprint "eagle-import:HECTOR_WATCH_1_TP20R")
      (libsource (lib "eagle-import") (part "HECTOR_WATCH_1_TPTP20R"))
    )
    (comp (ref "TP_OP")
      (value "HECTOR_WATCH_1_TPTP20R")
      (footprint "eagle-import:HECTOR_WATCH_1_TP20R")
      (libsource (lib "eagle-import") (part "HECTOR_WATCH_1_TPTP20R"))
    )
    (comp (ref "TP_RESET")
      (value "HECTOR_WATCH_1_TPTP20R")
      (footprint "eagle-import:HECTOR_WATCH_1_TP20R")
      (libsource (lib "eagle-import") (part "HECTOR_WATCH_1_TPTP20R"))
    )
    (comp (ref "TP_SCL")
      (value "HECTOR_WATCH_1_TPTP20R")
      (footprint "eagle-import:HECTOR_WATCH_1_TP20R")
      (libsource (lib "eagle-import") (part "HECTOR_WATCH_1_TPTP20R"))
    )
    (comp (ref "TP_SDA")
      (value "HECTOR_WATCH_1_TPTP20R")
      (footprint "eagle-import:HECTOR_WATCH_1_TP20R")
      (libsource (lib "eagle-import") (part "HECTOR_WATCH_1_TPTP20R"))
    )
    (comp (ref "TP_SW0")
      (value "HECTOR_WATCH_1_TPTP20R")
      (footprint "eagle-import:HECTOR_WATCH_1_TP20R")
      (libsource (lib "eagle-import") (part "HECTOR_WATCH_1_TPTP20R"))
    )
    (comp (ref "TP_SWDCLK")
      (value "HECTOR_WATCH_1_TPTP20R")
      (footprint "eagle-import:HECTOR_WATCH_1_TP20R")
      (libsource (lib "eagle-import") (part "HECTOR_WATCH_1_TPTP20R"))
    )
    (comp (ref "TP_SWDIO")
      (value "HECTOR_WATCH_1_TPTP20R")
      (footprint "eagle-import:HECTOR_WATCH_1_TP20R")
      (libsource (lib "eagle-import") (part "HECTOR_WATCH_1_TPTP20R"))
    )
    (comp (ref "TP_VBAT")
      (value "HECTOR_WATCH_1_TPTP20R")
      (footprint "eagle-import:HECTOR_WATCH_1_TP20R")
      (libsource (lib "eagle-import") (part "HECTOR_WATCH_1_TPTP20R"))
    )
    (comp (ref "U$1")
      (value "NORDIC_NRF_4_NRF52840_QF")
      (footprint "eagle-import:NORDIC_NRF_4_AQFN50P700X700X85_HS-74N")
      (libsource (lib "eagle-import") (part "NORDIC_NRF_4_NRF52840_QF"))
    )
    (comp (ref "U1")
      (value "ESP32_C6_LIBRARY_MAX17048G+T10")
      (footprint "eagle-import:ESP32_C6_LIBRARY_SON50P200X200X80-9N")
      (fields (field (name "MF") "Analog Devices") (field (name "MP") "MAX17048G+T10"))
      (libsource (lib "eagle-import") (part "ESP32_C6_LIBRARY_MAX17048G+T10"))
    )
    (comp (ref "X1")
      (value "32MHz")
      (footprint "eagle-import:NORDIC_NRF_BT-XTAL_2016_N")
      (libsource (lib "eagle-import") (part "NORDIC_NRF_XTAL_32MHZ"))
    )
    (comp (ref "X2")
      (value "32.768kHz")
      (footprint "eagle-import:NORDIC_NRF_1_XTAL_3215_N")
      (libsource (lib "eagle-import") (part "NORDIC_NRF_1_XTAL_32KHZ"))
    )
  )
  (nets
    (net (code "1") (name "/DEC1") (class "Default")
      (node (ref "C5") (pin "1") (pinfunction "1_1") (pintype "passive"))
      (node (ref "U$1") (pin "P$C1") (pinfunction "DEC1_P$C1") (pintype "power_in"))
    )
    (net (code "2") (name "/DEC3") (class "Default")
      (node (ref "C11") (pin "1") (pinfunction "1_1") (pintype "passive"))
      (node (ref "U$1") (pin "P$D23") (pinfunction "DEC3_P$D23") (pintype "bidirectional"))
    )
    (net (code "3") (name "/DEC4_6") (class "Default")
      (node (ref "C10") (pin "1") (pinfunction "1_1") (pintype "passive"))
      (node (ref "C15") (pin "1") (pinfunction "1_1") (pintype "passive"))
      (node (ref "C16") (pin "1") (pinfunction "1_1") (pintype "passive"))
      (node (ref "L3") (pin "2") (pinfunction "2_2") (pintype "bidirectional"))
      (node (ref "U$1") (pin "P$B5") (pinfunction "DEC4_P$B5") (pintype "power_in"))
      (node (ref "U$1") (pin "P$E24") (pinfunction "DEC6_P$E24") (pintype "bidirectional"))
    )
    (net (code "4") (name "/P0.00{slash}XL1") (class "Default")
      (node (ref "C17") (pin "2") (pinfunction "2_2") (pintype "passive"))
      (node (ref "U$1") (pin "P$D2") (pinfunction "P0.00/XL1_P$D2") (pintype "bidirectional"))
      (node (ref "X2") (pin "2") (pinfunction "2_2") (pintype "passive"))
    )
    (net (code "5") (name "/RF") (class "Default")
      (node (ref "ANT1") (pin "1") (pinfunction "FEED_1") (pintype "input"))
      (node (ref "C22") (pin "1") (pinfunction "1_1") (pintype "passive"))
      (node (ref "C4") (pin "1") (pinfunction "1_1") (pintype "passive"))
      (node (ref "L1") (pin "2") (pinfunction "2_2") (pintype "bidirectional"))
    )
    (net (code "6") (name "3V3") (class "Default")
      (node (ref "C12") (pin "1") (pinfunction "1_1") (pintype "passive"))
      (node (ref "C14") (pin "1") (pinfunction "1_1") (pintype "passive"))
      (node (ref "C19") (pin "1") (pinfunction "1_1") (pintype "passive"))
      (node (ref "C25") (pin "1") (pinfunction "1_1") (pintype "passive"))
      (node (ref "C33") (pin "1") (pinfunction "1_1") (pintype "passive"))
      (node (ref "C34") (pin "1") (pinfunction "1_1") (pintype "passive"))
      (node (ref "C6") (pin "1") (pinfunction "1_1") (pintype "passive"))
      (node (ref "C7") (pin "1") (pinfunction "1_1") (pintype "passive"))
      (node (ref "C8") (pin "1") (pinfunction "1_1") (pintype "passive"))
      (node (ref "IC2") (pin "E2") (pinfunction "VOUT_1_E2") (pintype "bidirectional"))
      (node (ref "IC2") (pin "E3") (pinfunction "VOUT_2_E3") (pintype "bidirectional"))
      (node (ref "IC3") (pin "10") (pinfunction "CSB_10") (pintype "bidirectional"))
      (node (ref "IC3") (pin "3") (pinfunction "VDDIO_3") (pintype "bidirectional"))
      (node (ref "IC3") (pin "7") (pinfunction "VDD_7") (pintype "bidirectional"))
      (node (ref "IC4") (pin "C2") (pinfunction "VDD_C2") (pintype "bidirectional"))
      (node (ref "J1") (pin "1") (pinfunction "1_1") (pintype "bidirectional"))
      (node (ref "Q1") (pin "2") (pinfunction "S_2") (pintype "bidirectional"))
      (node (ref "Q1") (pin "3") (pinfunction "D_3") (pintype "bidirectional"))
      (node (ref "R1") (pin "2") (pinfunction "2_2") (pintype "bidirectional"))
      (node (ref "R17") (pin "1") (pinfunction "1_1") (pintype "bidirectional"))
      (node (ref "R18") (pin "1") (pinfunction "1_1") (pintype "bidirectional"))
      (node (ref "R5") (pin "2") (pinfunction "2_2") (pintype "bidirectional"))
      (node (ref "R6") (pin "2") (pinfunction "2_2") (pintype "bidirectional"))
      (node (ref "R_PWR_EPD") (pin "2") (pinfunction "2_2") (pintype "bidirectional"))
      (node (ref "TP_3.3V") (pin "TP") (pinfunction "TP_TP") (pintype "input"))
      (node (ref "TP_3V3") (pin "TP") (pinfunction "TP_TP") (pintype "input"))
      (node (ref "U$1") (pin "P$A22") (pinfunction "VDD_P$A22") (pintype "power_in"))
      (node (ref "U$1") (pin "P$AD14") (pinfunction "VDD_P$AD14") (pintype "power_in"))
      (node (ref "U$1") (pin "P$AD23") (pinfunction "VDD_P$AD23") (pintype "power_in"))
      (node (ref "U$1") (pin "P$B1") (pinfunction "VDD_P$B1") (pintype "power_in"))
      (node (ref "U$1") (pin "P$W1") (pinfunction "VDD_P$W1") (pintype "power_in"))
      (node (ref "U$1") (pin "P$Y2") (pinfunction "VDDH_P$Y2") (pintype "power_in"))
    )
    (net (code "7") (name "ALERT") (class "Default")
      (node (ref "U$1") (pin "P$J24") (pinfunction "P0.10/NFC2_P$J24") (pintype "bidirectional"))
      (node (ref "U1") (pin "5") (pinfunction "~{ALERT}_5") (pintype "output"))
    )
    (net (code "8") (name "D+") (class "Default")
      (node (ref "D1") (pin "4") (pinfunction "I/O2_2_4") (pintype "bidirectional"))
      (node (ref "U$1") (pin "P$AD6") (pinfunction "D+_P$AD6") (pintype "bidirectional"))
    )
    (net (code "9") (name "D-") (class "Default")
      (node (ref "D1") (pin "6") (pinfunction "I/O1_2_6") (pintype "bidirectional"))
      (node (ref "U$1") (pin "P$AD4") (pinfunction "D-_P$AD4") (pintype "bidirectional"))
    )
    (net (code "10") (name "DN") (class "Default")
      (node (ref "D1") (pin "1") (pinfunction "I/O1_1_1") (pintype "bidirectional"))
      (node (ref "J3") (pin "A7") (pinfunction "DN1_A7") (pintype "bidirectional"))
      (node (ref "J3") (pin "B7") (pinfunction "DN2_B7") (pintype "bidirectional"))
    )
    (net (code "11") (name "DP") (class "Default")
      (node (ref "D1") (pin "3") (pinfunction "I/O2_1_3") (pintype "bidirectional"))
      (node (ref "J3") (pin "A6") (pinfunction "DP1_A6") (pintype "bidirectional"))
      (node (ref "J3") (pin "B6") (pinfunction "DP2_B6") (pintype "bidirectional"))
    )
    (net (code "12") (name "EPD_3V3") (class "Default")
      (node (ref "C1-EP-DR") (pin "1") (pinfunction "1_1") (pintype "passive"))
      (node (ref "EPD_C5") (pin "2") (pinfunction "2_2") (pintype "passive"))
      (node (ref "J2") (pin "15") (pinfunction "15_15") (pintype "bidirectional"))
      (node (ref "J2") (pin "16") (pinfunction "16_16") (pintype "bidirectional"))
      (node (ref "L5") (pin "1") (pinfunction "1_1") (pintype "bidirectional"))
    )
    (net (code "13") (name "EPD_BUSY") (class "Default")
      (node (ref "J2") (pin "9") (pinfunction "9_9") (pintype "bidirectional"))
      (node (ref "U$1") (pin "P$AD12") (pinfunction "P0.17_P$AD12") (pintype "bidirectional"))
    )
    (net (code "14") (name "EPD_CS") (class "Default")
      (node (ref "J2") (pin "12") (pinfunction "12_12") (pintype "bidirectional"))
      (node (ref "U$1") (pin "P$K2") (pinfunction "P0.05/AIN3_P$K2") (pintype "bidirectional"))
    )
    (net (code "15") (name "EPD_DC") (class "Default")
      (node (ref "J2") (pin "11") (pinfunction "11_11") (pintype "bidirectional"))
      (node (ref "U$1") (pin "P$AD10") (pinfunction "P0.15_P$AD10") (pintype "bidirectional"))
    )
    (net (code "16") (name "EPD_RST") (class "Default")
      (node (ref "J2") (pin "10") (pinfunction "10_10") (pintype "bidirectional"))
      (node (ref "U$1") (pin "P$AC11") (pinfunction "P0.16_P$AC11") (pintype "bidirectional"))
    )
    (net (code "17") (name "GDR") (class "Default")
      (node (ref "J2") (pin "2") (pinfunction "2_2") (pintype "bidirectional"))
      (node (ref "Q3") (pin "1") (pinfunction "G_1") (pintype "bidirectional"))
      (node (ref "R2_EP_DR") (pin "2") (pinfunction "2_2") (pintype "bidirectional"))
    )
    (net (code "18") (name "GND") (class "Default")
      (node (ref "C1") (pin "2") (pinfunction "2_2") (pintype "passive"))
      (node (ref "C1-EP-DR") (pin "2") (pinfunction "2_2") (pintype "passive"))
      (node (ref "C10") (pin "2") (pinfunction "2_2") (pintype "passive"))
      (node (ref "C11") (pin "2") (pinfunction "2_2") (pintype "passive"))
      (node (ref "C12") (pin "2") (pinfunction "2_2") (pintype "passive"))
      (node (ref "C13") (pin "2") (pinfunction "2_2") (pintype "passive"))
      (node (ref "C14") (pin "2") (pinfunction "2_2") (pintype "passive"))
      (node (ref "C15") (pin "2") (pinfunction "2_2") (pintype "passive"))
      (node (ref "C16") (pin "2") (pinfunction "2_2") (pintype "passive"))
      (node (ref "C19") (pin "2") (pinfunction "2_2") (pintype "passive"))
      (node (ref "C2") (pin "2") (pinfunction "2_2") (pintype "passive"))
      (node (ref "C20") (pin "2") (pinfunction "2_2") (pintype "passive"))
      (node (ref "C21") (pin "2") (pinfunction "2_2") (pintype "passive"))
      (node (ref "C22") (pin "2") (pinfunction "2_2") (pintype "passive"))
      (node (ref "C23") (pin "1") (pinfunction "1_1") (pintype "passive"))
      (node (ref "C24") (pin "1") (pinfunction "1_1") (pintype "passive"))
      (node (ref "C25") (pin "2") (pinfunction "2_2") (pintype "passive"))
      (node (ref "C27") (pin "2") (pinfunction "2_2") (pintype "passive"))
      (node (ref "C29") (pin "2") (pinfunction "2_2") (pintype "passive"))
      (node (ref "C3") (pin "2") (pinfunction "2_2") (pintype "passive"))
      (node (ref "C30") (pin "2") (pinfunction "2_2") (pintype "passive"))
      (node (ref "C31") (pin "2") (pinfunction "2_2") (pintype "passive"))
      (node (ref "C32") (pin "2") (pinfunction "2_2") (pintype "passive"))
      (node (ref "C33") (pin "2") (pinfunction "2_2") (pintype "passive"))
      (node (ref "C34") (pin "2") (pinfunction "2_2") (pintype "passive"))
      (node (ref "C37") (pin "2") (pinfunction "2_2") (pintype "passive"))
      (node (ref "C38") (pin "2") (pinfunction "2_2") (pintype "passive"))
      (node (ref "C39") (pin "2") (pinfunction "2_2") (pintype "passive"))
      (node (ref "C4") (pin "2") (pinfunction "2_2") (pintype "passive"))
      (node (ref "C42") (pin "2") (pinfunction "2_2") (pintype "passive"))
      (node (ref "C43") (pin "2") (pinfunction "2_2") (pintype "passive"))
      (node (ref "C5") (pin "2") (pinfunction "2_2") (pintype "passive"))
      (node (ref "C6") (pin "2") (pinfunction "2_2") (pintype "passive"))
      (node (ref "C7") (pin "2") (pinfunction "2_2") (pintype "passive"))
      (node (ref "C8") (pin "2") (pinfunction "2_2") (pintype "passive"))
      (node (ref "C9") (pin "2") (pinfunction "2_2") (pintype "passive"))
      (node (ref "D1") (pin "2") (pinfunction "GND_2") (pintype "bidirectional"))
      (node (ref "D4") (pin "1") (pinfunction "K_1") (pintype "bidirectional"))
      (node (ref "EPD_C1") (pin "1") (pinfunction "1_1") (pintype "passive"))
      (node (ref "EPD_C10") (pin "1") (pinfunction "1_1") (pintype "passive"))
      (node (ref "EPD_C11") (pin "1") (pinfunction "1_1") (pintype "passive"))
      (node (ref "EPD_C12") (pin "1") (pinfunction "1_1") (pintype "passive"))
      (node (ref "EPD_C2") (pin "1") (pinfunction "1_1") (pintype "passive"))
      (node (ref "EPD_C5") (pin "1") (pinfunction "1_1") (pintype "passive"))
      (node (ref "EPD_C6") (pin "1") (pinfunction "1_1") (pintype "passive"))
      (node (ref "EPD_C7") (pin "1") (pinfunction "1_1") (pintype "passive"))
      (node (ref "EPD_C8") (pin "1") (pinfunction "1_1") (pintype "passive"))
      (node (ref "EPD_C9") (pin "1") (pinfunction "1_1") (pintype "passive"))
      (node (ref "IC1") (pin "D2") (pinfunction "GND_D2") (pintype "bidirectional"))
      (node (ref "IC2") (pin "B1") (pinfunction "VSEL_B1") (pintype "bidirectional"))
      (node (ref "IC2") (pin "C1") (pinfunction "AGND_C1") (pintype "bidirectional"))
      (node (ref "IC2") (pin "C2") (pinfunction "PGND_1_C2") (pintype "bidirectional"))
      (node (ref "IC2") (pin "C3") (pinfunction "PGND_2_C3") (pintype "bidirectional"))
      (node (ref "IC3") (pin "8") (pinfunction "GNDIO_8") (pintype "bidirectional"))
      (node (ref "IC3") (pin "9") (pinfunction "GND_9") (pintype "bidirectional"))
      (node (ref "IC4") (pin "B1") (pinfunction "IN/TRIG_B1") (pintype "bidirectional"))
      (node (ref "IC4") (pin "B3") (pinfunction "GND_B3") (pintype "bidirectional"))
      (node (ref "J1") (pin "3") (pinfunction "3_3") (pintype "bidirectional"))
      (node (ref "J1") (pin "5") (pinfunction "5_5") (pintype "bidirectional"))
      (node (ref "J2") (pin "17") (pinfunction "17_17") (pintype "bidirectional"))
      (node (ref "J2") (pin "8") (pinfunction "8_8") (pintype "bidirectional"))
      (node (ref "J2") (pin "MP1") (pinfunction "MP1_MP1") (pintype "bidirectional"))
      (node (ref "J2") (pin "MP2") (pinfunction "MP2_MP2") (pintype "bidirectional"))
      (node (ref "J3") (pin "A12_B1") (pinfunction "GND_A12_B1") (pintype "power_in"))
      (node (ref "J3") (pin "A1_B12") (pinfunction "GND_A1_B12") (pintype "power_in"))
      (node (ref "J3") (pin "SH1") (pinfunction "SHIELD_SH1") (pintype "passive"))
      (node (ref "J3") (pin "SH2") (pinfunction "SHIELD_SH2") (pintype "passive"))
      (node (ref "J3") (pin "SH3") (pinfunction "SHIELD_SH3") (pintype "passive"))
      (node (ref "J3") (pin "SH4") (pinfunction "SHIELD_SH4") (pintype "passive"))
      (node (ref "R1_USB") (pin "1") (pinfunction "1_1") (pintype "bidirectional"))
      (node (ref "R2_EP_DR") (pin "1") (pinfunction "1_1") (pintype "bidirectional"))
      (node (ref "R2_USB") (pin "2") (pinfunction "2_2") (pintype "bidirectional"))
      (node (ref "R3") (pin "2") (pinfunction "2_2") (pintype "bidirectional"))
      (node (ref "R9") (pin "1") (pinfunction "1_1") (pintype "bidirectional"))
      (node (ref "R_TYPE_SEL") (pin "1") (pinfunction "1_1") (pintype "bidirectional"))
      (node (ref "SJ1") (pin "1") (pinfunction "1_1") (pintype "passive"))
      (node (ref "SW1") (pin "1") (pinfunction "1_1") (pintype "passive"))
      (node (ref "SW2") (pin "1") (pinfunction "1_1") (pintype "passive"))
      (node (ref "SW3") (pin "1") (pinfunction "1_1") (pintype "passive"))
      (node (ref "TP_BAT_GND") (pin "TP") (pinfunction "TP_TP") (pintype "input"))
      (node (ref "TP_GND") (pin "TP") (pinfunction "TP_TP") (pintype "input"))
      (node (ref "U$1") (pin "P$74") (pinfunction "VSS_PAD_P$74") (pintype "bidirectional"))
      (node (ref "U$1") (pin "P$75") (pinfunction "VSS_PAD_P$75") (pintype "bidirectional"))
      (node (ref "U$1") (pin "P$76") (pinfunction "VSS_PAD_P$76") (pintype "bidirectional"))
      (node (ref "U$1") (pin "P$77") (pinfunction "VSS_PAD_P$77") (pintype "bidirectional"))
      (node (ref "U$1") (pin "P$78") (pinfunction "VSS_PAD_P$78") (pintype "bidirectional"))
      (node (ref "U$1") (pin "P$79") (pinfunction "VSS_PAD_P$79") (pintype "bidirectional"))
      (node (ref "U$1") (pin "P$80") (pinfunction "VSS_PAD_P$80") (pintype "bidirectional"))
      (node (ref "U$1") (pin "P$81") (pinfunction "VSS_PAD_P$81") (pintype "bidirectional"))
      (node (ref "U$1") (pin "P$82") (pinfunction "VSS_PAD_P$82") (pintype "bidirectional"))
      (node (ref "U$1") (pin "P$83") (pinfunction "VSS_PAD_P$83") (pintype "bidirectional"))
      (node (ref "U$1") (pin "P$84") (pinfunction "VSS_PAD_P$84") (pintype "bidirectional"))
      (node (ref "U$1") (pin "P$85") (pinfunction "VSS_PAD_P$85") (pintype "bidirectional"))
      (node (ref "U$1") (pin "P$86") (pinfunction "VSS_PAD_P$86") (pintype "bidirectional"))
      (node (ref "U$1") (pin "P$87") (pinfunction "VSS_PAD_P$87") (pintype "bidirectional"))
      (node (ref "U$1") (pin "P$88") (pinfunction "VSS_PAD_P$88") (pintype "bidirectional"))
      (node (ref "U$1") (pin "P$89") (pinfunction "VSS_PAD_P$89") (pintype "bidirectional"))
      (node (ref "U$1") (pin "P$90") (pinfunction "VSS_PAD_P$90") (pintype "bidirectional"))
      (node (ref "U$1") (pin "P$B7") (pinfunction "VSS_P$B7") (pintype "power_in"))
      (node (ref "U$1") (pin "P$F23") (pinfunction "VSS_PA_P$F23") (pintype "bidirectional"))
      (node (ref "U1") (pin "1") (pinfunction "CTG_1") (pintype "power_in"))
      (node (ref "U1") (pin "4") (pinfunction "GND_4") (pintype "power_in"))
      (node (ref "U1") (pin "6") (pinfunction "QSTRT_6") (pintype "input"))
      (node (ref "U1") (pin "9") (pinfunction "EP_9") (pintype "power_in"))
      (node (ref "X1") (pin "2") (pinfunction "2_2") (pintype "passive"))
      (node (ref "X1") (pin "4") (pinfunction "4_4") (pintype "passive"))
    )
    (net (code "19") (name "HAPTIC_EN") (class "Default")
      (node (ref "IC4") (pin "A1") (pinfunction "EN_A1") (pintype "bidirectional"))
      (node (ref "U$1") (pin "P$U1") (pinfunction "P0.12_P$U1") (pintype "bidirectional"))
    )
    (net (code "20") (name "IMU_INT1") (class "Default")
      (node (ref "IC3") (pin "5") (pinfunction "INT1_5") (pintype "bidirectional"))
      (node (ref "U$1") (pin "P$N1") (pinfunction "P0.08_P$N1") (pintype "bidirectional"))
    )
    (net (code "21") (name "IMU_INT2") (class "Default")
      (node (ref "IC3") (pin "6") (pinfunction "INT2_6") (pintype "bidirectional"))
      (node (ref "U$1") (pin "P$P2") (pinfunction "P1.08_P$P2") (pintype "bidirectional"))
    )
    (net (code "22") (name "LX1") (class "Default")
      (node (ref "IC2") (pin "B2") (pinfunction "SW1_1_B2") (pintype "bidirectional"))
      (node (ref "IC2") (pin "B3") (pinfunction "SW1_2_B3") (pintype "bidirectional"))
      (node (ref "L7") (pin "1") (pinfunction "1_1") (pintype "bidirectional"))
    )
    (net (code "23") (name "LX2") (class "Default")
      (node (ref "IC2") (pin "D2") (pinfunction "SW2_1_D2") (pintype "bidirectional"))
      (node (ref "IC2") (pin "D3") (pinfunction "SW2_2_D3") (pintype "bidirectional"))
      (node (ref "L7") (pin "2") (pinfunction "2_2") (pintype "bidirectional"))
    )
    (net (code "24") (name "MOSI") (class "Default")
      (node (ref "J2") (pin "14") (pinfunction "14_14") (pintype "bidirectional"))
      (node (ref "U$1") (pin "P$B13") (pinfunction "P0.03/AIN1_P$B13") (pintype "bidirectional"))
    )
    (net (code "25") (name "Net-(D2-K)") (class "Default")
      (node (ref "C2-EP-DR") (pin "1") (pinfunction "1_1") (pintype "passive"))
      (node (ref "D2") (pin "1") (pinfunction "K_1") (pintype "bidirectional"))
      (node (ref "D4") (pin "2") (pinfunction "A_2") (pintype "bidirectional"))
    )
    (net (code "26") (name "Net-(D5-A)") (class "Default")
      (node (ref "C2-EP-DR") (pin "2") (pinfunction "2_2") (pintype "passive"))
      (node (ref "D5") (pin "2") (pinfunction "A_2") (pintype "bidirectional"))
      (node (ref "L5") (pin "2") (pinfunction "2_2") (pintype "bidirectional"))
      (node (ref "Q3") (pin "3") (pinfunction "D_3") (pintype "bidirectional"))
    )
    (net (code "27") (name "Net-(EPD_C1-Pad2)") (class "Default")
      (node (ref "EPD_C1") (pin "2") (pinfunction "2_2") (pintype "passive"))
      (node (ref "J2") (pin "5") (pinfunction "5_5") (pintype "bidirectional"))
    )
    (net (code "28") (name "Net-(EPD_C2-Pad2)") (class "Default")
      (node (ref "EPD_C2") (pin "2") (pinfunction "2_2") (pintype "passive"))
      (node (ref "J2") (pin "4") (pinfunction "4_4") (pintype "bidirectional"))
    )
    (net (code "29") (name "Net-(EPD_C6-Pad2)") (class "Default")
      (node (ref "EPD_C6") (pin "2") (pinfunction "2_2") (pintype "passive"))
      (node (ref "J2") (pin "18") (pinfunction "18_18") (pintype "bidirectional"))
    )
    (net (code "30") (name "Net-(EPD_C7-Pad2)") (class "Default")
      (node (ref "EPD_C7") (pin "2") (pinfunction "2_2") (pintype "passive"))
      (node (ref "J2") (pin "19") (pinfunction "19_19") (pintype "bidirectional"))
    )
    (net (code "31") (name "Net-(EPD_C8-Pad2)") (class "Default")
      (node (ref "EPD_C8") (pin "2") (pinfunction "2_2") (pintype "passive"))
      (node (ref "J2") (pin "20") (pinfunction "20_20") (pintype "bidirectional"))
    )
    (net (code "32") (name "Net-(EPD_C11-Pad2)") (class "Default")
      (node (ref "EPD_C11") (pin "2") (pinfunction "2_2") (pintype "passive"))
      (node (ref "J2") (pin "23") (pinfunction "23_23") (pintype "bidirectional"))
    )
    (net (code "33") (name "Net-(EPD_C12-Pad2)") (class "Default")
      (node (ref "EPD_C12") (pin "2") (pinfunction "2_2") (pintype "passive"))
      (node (ref "J2") (pin "24") (pinfunction "24_24") (pintype "bidirectional"))
    )
    (net (code "34") (name "Net-(IC1-TS{slash}MR)") (class "Default")
      (node (ref "IC1") (pin "D1") (pinfunction "TS/MR_D1") (pintype "bidirectional"))
      (node (ref "R9") (pin "2") (pinfunction "2_2") (pintype "bidirectional"))
    )
    (net (code "35") (name "Net-(IC2-SCL)") (class "Default")
      (node (ref "IC2") (pin "D1") (pinfunction "SCL_D1") (pintype "bidirectional"))
      (node (ref "R4") (pin "1") (pinfunction "1_1") (pintype "bidirectional"))
    )
    (net (code "36") (name "Net-(IC2-SDA)") (class "Default")
      (node (ref "IC2") (pin "E1") (pinfunction "SDA_E1") (pintype "bidirectional"))
      (node (ref "R2") (pin "1") (pinfunction "1_1") (pintype "bidirectional"))
    )
    (net (code "37") (name "Net-(IC3-SDO)") (class "Default")
      (node (ref "IC3") (pin "1") (pinfunction "SDO_1") (pintype "bidirectional"))
      (node (ref "R3") (pin "1") (pinfunction "1_1") (pintype "bidirectional"))
    )
    (net (code "38") (name "Net-(IC4-REG)") (class "Default")
      (node (ref "C32") (pin "1") (pinfunction "1_1") (pintype "passive"))
      (node (ref "IC4") (pin "A2") (pinfunction "REG_A2") (pintype "bidirectional"))
    )
    (net (code "39") (name "Net-(J3-CC1)") (class "Default")
      (node (ref "J3") (pin "A5") (pinfunction "CC1_A5") (pintype "bidirectional"))
      (node (ref "R1_USB") (pin "2") (pinfunction "2_2") (pintype "bidirectional"))
    )
    (net (code "40") (name "Net-(J3-CC2)") (class "Default")
      (node (ref "J3") (pin "B5") (pinfunction "CC2_B5") (pintype "bidirectional"))
      (node (ref "R2_USB") (pin "1") (pinfunction "1_1") (pintype "bidirectional"))
    )
    (net (code "41") (name "Net-(L2-Pad2)") (class "Default")
      (node (ref "L2") (pin "2") (pinfunction "2_2") (pintype "bidirectional"))
      (node (ref "L3") (pin "1") (pinfunction "1_1") (pintype "bidirectional"))
    )
    (net (code "42") (name "Net-(R1_EP_DR-Pad1)") (class "Default")
      (node (ref "R1_EP_DR") (pin "1") (pinfunction "1_1") (pintype "bidirectional"))
      (node (ref "R_TYPE_SEL") (pin "2") (pinfunction "2_2") (pintype "bidirectional"))
      (node (ref "SJ1") (pin "2") (pinfunction "2_2") (pintype "passive"))
    )
    (net (code "43") (name "Net-(U$1-ANT)") (class "Default")
      (node (ref "C3") (pin "1") (pinfunction "1_1") (pintype "passive"))
      (node (ref "L1") (pin "1") (pinfunction "1_1") (pintype "bidirectional"))
      (node (ref "U$1") (pin "P$H23") (pinfunction "ANT_P$H23") (pintype "bidirectional"))
    )
    (net (code "44") (name "Net-(U$1-DCC)") (class "Default")
      (node (ref "L2") (pin "1") (pinfunction "1_1") (pintype "bidirectional"))
      (node (ref "U$1") (pin "P$B3") (pinfunction "DCC_P$B3") (pintype "output"))
    )
    (net (code "45") (name "Net-(U$1-DEC2)") (class "Default")
      (node (ref "C13") (pin "1") (pinfunction "1_1") (pintype "passive"))
      (node (ref "U$1") (pin "P$A18") (pinfunction "DEC2_P$A18") (pintype "bidirectional"))
    )
    (net (code "46") (name "Net-(U$1-DEC3V3)") (class "Default")
      (node (ref "C20") (pin "1") (pinfunction "1_1") (pintype "passive"))
      (node (ref "U$1") (pin "P$AC5") (pinfunction "DEC3V3_P$AC5") (pintype "bidirectional"))
    )
    (net (code "47") (name "Net-(U$1-DEC5)") (class "Default")
      (node (ref "C9") (pin "1") (pinfunction "1_1") (pintype "passive"))
      (node (ref "U$1") (pin "P$N24") (pinfunction "DEC5_P$N24") (pintype "bidirectional"))
    )
    (net (code "48") (name "Net-(U$1-XC1)") (class "Default")
      (node (ref "C1") (pin "1") (pinfunction "1_1") (pintype "passive"))
      (node (ref "U$1") (pin "P$B24") (pinfunction "XC1_P$B24") (pintype "input"))
      (node (ref "X1") (pin "1") (pinfunction "1_1") (pintype "passive"))
    )
    (net (code "49") (name "Net-(U$1-XC2)") (class "Default")
      (node (ref "C2") (pin "1") (pinfunction "1_1") (pintype "passive"))
      (node (ref "U$1") (pin "P$A23") (pinfunction "XC2_P$A23") (pintype "output"))
      (node (ref "X1") (pin "3") (pinfunction "3_3") (pintype "passive"))
    )
    (net (code "50") (name "OUT+") (class "Default")
      (node (ref "IC4") (pin "A3") (pinfunction "OUT+_A3") (pintype "bidirectional"))
      (node (ref "TP_OP") (pin "TP") (pinfunction "TP_TP") (pintype "input"))
    )
    (net (code "51") (name "OUT-") (class "Default")
      (node (ref "IC4") (pin "C3") (pinfunction "OUT-_C3") (pintype "bidirectional"))
      (node (ref "TP_ON") (pin "TP") (pinfunction "TP_TP") (pintype "input"))
    )
    (net (code "52") (name "P0.01{slash}XL2") (class "Default")
      (node (ref "C17") (pin "1") (pinfunction "1_1") (pintype "passive"))
      (node (ref "C18") (pin "1") (pinfunction "1_1") (pintype "passive"))
      (node (ref "C18") (pin "2") (pinfunction "2_2") (pintype "passive"))
      (node (ref "U$1") (pin "P$F2") (pinfunction "P0.01/XL2_P$F2") (pintype "bidirectional"))
      (node (ref "X2") (pin "1") (pinfunction "1_1") (pintype "passive"))
    )
    (net (code "53") (name "P0.04") (class "Default")
      (node (ref "U$1") (pin "P$J1") (pinfunction "P0.04/AIN2_P$J1") (pintype "bidirectional"))
    )
    (net (code "54") (name "P0.09") (class "Default")
      (node (ref "U$1") (pin "P$L24") (pinfunction "P0.09/NFC1_P$L24") (pintype "bidirectional"))
    )
    (net (code "55") (name "P0.13") (class "Default")
      (node (ref "C30") (pin "1") (pinfunction "1_1") (pintype "passive"))
      (node (ref "R1") (pin "1") (pinfunction "1_1") (pintype "bidirectional"))
      (node (ref "SW1") (pin "2") (pinfunction "2_2") (pintype "passive"))
      (node (ref "U$1") (pin "P$AD8") (pinfunction "P0.13_P$AD8") (pintype "bidirectional"))
    )
    (net (code "56") (name "P0.14") (class "Default")
      (node (ref "C31") (pin "1") (pinfunction "1_1") (pintype "passive"))
      (node (ref "R5") (pin "1") (pinfunction "1_1") (pintype "bidirectional"))
      (node (ref "SW2") (pin "2") (pinfunction "2_2") (pintype "passive"))
      (node (ref "U$1") (pin "P$AC9") (pinfunction "P0.14_P$AC9") (pintype "bidirectional"))
    )
    (net (code "57") (name "P0.19") (class "Default")
      (node (ref "U$1") (pin "P$AC15") (pinfunction "P0.19_P$AC15") (pintype "bidirectional"))
    )
    (net (code "58") (name "P0.20") (class "Default")
      (node (ref "U$1") (pin "P$AD16") (pinfunction "P0.20_P$AD16") (pintype "bidirectional"))
    )
    (net (code "59") (name "P0.21") (class "Default")
      (node (ref "U$1") (pin "P$AC17") (pinfunction "P0.21_P$AC17") (pintype "bidirectional"))
    )
    (net (code "60") (name "P0.22") (class "Default")
      (node (ref "U$1") (pin "P$AD18") (pinfunction "P0.22_P$AD18") (pintype "bidirectional"))
    )
    (net (code "61") (name "P0.23") (class "Default")
      (node (ref "U$1") (pin "P$AC19") (pinfunction "P0.23_P$AC19") (pintype "bidirectional"))
    )
    (net (code "62") (name "P0.24") (class "Default")
      (node (ref "U$1") (pin "P$AD20") (pinfunction "P0.24_P$AD20") (pintype "bidirectional"))
    )
    (net (code "63") (name "P0.25") (class "Default")
      (node (ref "U$1") (pin "P$AC21") (pinfunction "P0.25_P$AC21") (pintype "bidirectional"))
    )
    (net (code "64") (name "P0.26") (class "Default")
      (node (ref "U$1") (pin "P$G1") (pinfunction "P0.26_P$G1") (pintype "bidirectional"))
    )
    (net (code "65") (name "P0.27") (class "Default")
      (node (ref "U$1") (pin "P$H2") (pinfunction "P0.27_P$H2") (pintype "bidirectional"))
    )
    (net (code "66") (name "P0.28") (class "Default")
      (node (ref "U$1") (pin "P$B11") (pinfunction "P0.28/AIN4_P$B11") (pintype "bidirectional"))
    )
    (net (code "67") (name "P0.29") (class "Default")
      (node (ref "U$1") (pin "P$A10") (pinfunction "P0.29/AIN5_P$A10") (pintype "bidirectional"))
    )
    (net (code "68") (name "P0.30") (class "Default")
      (node (ref "U$1") (pin "P$B9") (pinfunction "P0.30/AIN6_P$B9") (pintype "bidirectional"))
    )
    (net (code "69") (name "P0.31") (class "Default")
      (node (ref "U$1") (pin "P$A8") (pinfunction "P0.31/AIN7_P$A8") (pintype "bidirectional"))
    )
    (net (code "70") (name "P1.01") (class "Default")
      (node (ref "Q1") (pin "1") (pinfunction "G_1") (pintype "bidirectional"))
      (node (ref "R_PWR_EPD") (pin "1") (pinfunction "1_1") (pintype "bidirectional"))
      (node (ref "U$1") (pin "P$Y23") (pinfunction "P1.01_P$Y23") (pintype "bidirectional"))
    )
    (net (code "71") (name "P1.02") (class "Default")
      (node (ref "C29") (pin "1") (pinfunction "1_1") (pintype "passive"))
      (node (ref "R6") (pin "1") (pinfunction "1_1") (pintype "bidirectional"))
      (node (ref "SW3") (pin "2") (pinfunction "2_2") (pintype "passive"))
      (node (ref "U$1") (pin "P$W24") (pinfunction "P1.02_P$W24") (pintype "bidirectional"))
    )
    (net (code "72") (name "P1.03") (class "Default")
      (node (ref "U$1") (pin "P$V23") (pinfunction "P1.03_P$V23") (pintype "bidirectional"))
    )
    (net (code "73") (name "P1.04") (class "Default")
      (node (ref "U$1") (pin "P$U24") (pinfunction "P1.04_P$U24") (pintype "bidirectional"))
    )
    (net (code "74") (name "P1.05") (class "Default")
      (node (ref "U$1") (pin "P$T23") (pinfunction "P1.05_P$T23") (pintype "bidirectional"))
    )
    (net (code "75") (name "P1.06") (class "Default")
      (node (ref "U$1") (pin "P$R24") (pinfunction "P1.06_P$R24") (pintype "bidirectional"))
    )
    (net (code "76") (name "P1.07") (class "Default")
      (node (ref "U$1") (pin "P$P23") (pinfunction "P1.07_P$P23") (pintype "bidirectional"))
    )
    (net (code "77") (name "P1.09") (class "Default")
      (node (ref "U$1") (pin "P$R1") (pinfunction "P1.09_P$R1") (pintype "bidirectional"))
    )
    (net (code "78") (name "P1.10") (class "Default")
      (node (ref "U$1") (pin "P$A20") (pinfunction "P1.10_P$A20") (pintype "bidirectional"))
    )
    (net (code "79") (name "P1.11") (class "Default")
      (node (ref "U$1") (pin "P$B19") (pinfunction "P1.11_P$B19") (pintype "bidirectional"))
    )
    (net (code "80") (name "P1.12") (class "Default")
      (node (ref "U$1") (pin "P$B17") (pinfunction "P1.12_P$B17") (pintype "bidirectional"))
    )
    (net (code "81") (name "P1.13") (class "Default")
      (node (ref "U$1") (pin "P$A16") (pinfunction "P1.13_P$A16") (pintype "bidirectional"))
    )
    (net (code "82") (name "P1.14") (class "Default")
      (node (ref "U$1") (pin "P$B15") (pinfunction "P1.14_P$B15") (pintype "bidirectional"))
    )
    (net (code "83") (name "P1.15") (class "Default")
      (node (ref "U$1") (pin "P$A14") (pinfunction "P1.15_P$A14") (pintype "bidirectional"))
    )
    (net (code "84") (name "PMIC_INT") (class "Default")
      (node (ref "IC1") (pin "A1") (pinfunction "~{INT}_A1") (pintype "bidirectional"))
      (node (ref "U$1") (pin "P$T2") (pinfunction "P0.11_P$T2") (pintype "bidirectional"))
    )
    (net (code "85") (name "PREVGH") (class "Default")
      (node (ref "D5") (pin "1") (pinfunction "K_1") (pintype "bidirectional"))
      (node (ref "EPD_C9") (pin "2") (pinfunction "2_2") (pintype "passive"))
      (node (ref "J2") (pin "21") (pinfunction "21_21") (pintype "bidirectional"))
    )
    (net (code "86") (name "PREVGL") (class "Default")
      (node (ref "D2") (pin "2") (pinfunction "A_2") (pintype "bidirectional"))
      (node (ref "EPD_C10") (pin "2") (pinfunction "2_2") (pintype "passive"))
      (node (ref "J2") (pin "22") (pinfunction "22_22") (pintype "bidirectional"))
    )
    (net (code "87") (name "RESE") (class "Default")
      (node (ref "J2") (pin "3") (pinfunction "3_3") (pintype "bidirectional"))
      (node (ref "Q3") (pin "2") (pinfunction "S_2") (pintype "bidirectional"))
      (node (ref "R1_EP_DR") (pin "2") (pinfunction "2_2") (pintype "bidirectional"))
    )
    (net (code "88") (name "RESET") (class "Default")
      (node (ref "J1") (pin "6") (pinfunction "6_6") (pintype "bidirectional"))
      (node (ref "TP_RESET") (pin "TP") (pinfunction "TP_TP") (pintype "input"))
      (node (ref "U$1") (pin "P$AC13") (pinfunction "P0.18/RESET_P$AC13") (pintype "bidirectional"))
    )
    (net (code "89") (name "SCK") (class "Default")
      (node (ref "J2") (pin "13") (pinfunction "13_13") (pintype "bidirectional"))
      (node (ref "U$1") (pin "P$A12") (pinfunction "P0.02/AIN0_P$A12") (pintype "bidirectional"))
    )
    (net (code "90") (name "SCL") (class "Default")
      (node (ref "IC1") (pin "B1") (pinfunction "SCL_B1") (pintype "bidirectional"))
      (node (ref "IC3") (pin "12") (pinfunction "SCX_12") (pintype "bidirectional"))
      (node (ref "IC4") (pin "C1") (pinfunction "SCL_C1") (pintype "bidirectional"))
      (node (ref "R17") (pin "2") (pinfunction "2_2") (pintype "bidirectional"))
      (node (ref "R4") (pin "2") (pinfunction "2_2") (pintype "bidirectional"))
      (node (ref "TP_SCL") (pin "TP") (pinfunction "TP_TP") (pintype "input"))
      (node (ref "U$1") (pin "P$M2") (pinfunction "P0.07_P$M2") (pintype "bidirectional"))
      (node (ref "U1") (pin "7") (pinfunction "SCL_7") (pintype "input"))
    )
    (net (code "91") (name "SDA") (class "Default")
      (node (ref "IC1") (pin "C1") (pinfunction "SDA_C1") (pintype "bidirectional"))
      (node (ref "IC3") (pin "2") (pinfunction "SDX_2") (pintype "bidirectional"))
      (node (ref "IC4") (pin "B2") (pinfunction "SDA_B2") (pintype "bidirectional"))
      (node (ref "R18") (pin "2") (pinfunction "2_2") (pintype "bidirectional"))
      (node (ref "R2") (pin "2") (pinfunction "2_2") (pintype "bidirectional"))
      (node (ref "TP_SDA") (pin "TP") (pinfunction "TP_TP") (pintype "input"))
      (node (ref "U$1") (pin "P$L1") (pinfunction "P0.06_P$L1") (pintype "bidirectional"))
      (node (ref "U1") (pin "8") (pinfunction "SDA_8") (pintype "bidirectional"))
    )
    (net (code "92") (name "SWDCLK") (class "Default")
      (node (ref "J1") (pin "4") (pinfunction "4_4") (pintype "bidirectional"))
      (node (ref "TP_SWDCLK") (pin "TP") (pinfunction "TP_TP") (pintype "input"))
      (node (ref "U$1") (pin "P$AC24") (pinfunction "SWDIO_P$AC24") (pintype "bidirectional"))
    )
    (net (code "93") (name "SWDIO") (class "Default")
      (node (ref "J1") (pin "2") (pinfunction "2_2") (pintype "bidirectional"))
      (node (ref "TP_SWDIO") (pin "TP") (pinfunction "TP_TP") (pintype "input"))
      (node (ref "U$1") (pin "P$AA24") (pinfunction "SWDCLK_P$AA24") (pintype "input"))
    )
    (net (code "94") (name "SWO") (class "Default")
      (node (ref "TP_SW0") (pin "TP") (pinfunction "TP_TP") (pintype "input"))
      (node (ref "U$1") (pin "P$AD22") (pinfunction "P1.00_P$AD22") (pintype "bidirectional"))
    )
    (net (code "95") (name "VBAT") (class "Default")
      (node (ref "C27") (pin "1") (pinfunction "1_1") (pintype "passive"))
      (node (ref "C37") (pin "1") (pinfunction "1_1") (pintype "passive"))
      (node (ref "IC1") (pin "C2") (pinfunction "BAT_C2") (pintype "bidirectional"))
      (node (ref "TP_VBAT") (pin "TP") (pinfunction "TP_TP") (pintype "input"))
      (node (ref "U1") (pin "2") (pinfunction "CELL_2") (pintype "power_in"))
      (node (ref "U1") (pin "3") (pinfunction "VDD_3") (pintype "power_in"))
    )
    (net (code "96") (name "VBUS") (class "Default")
      (node (ref "C21") (pin "1") (pinfunction "1_1") (pintype "passive"))
      (node (ref "C38") (pin "1") (pinfunction "1_1") (pintype "passive"))
      (node (ref "C42") (pin "1") (pinfunction "1_1") (pintype "passive"))
      (node (ref "C43") (pin "1") (pinfunction "1_1") (pintype "passive"))
      (node (ref "D1") (pin "5") (pinfunction "VBUS_5") (pintype "bidirectional"))
      (node (ref "IC1") (pin "A2") (pinfunction "IN_A2") (pintype "bidirectional"))
      (node (ref "J3") (pin "A4_B9") (pinfunction "VBUS_A4_B9") (pintype "power_in"))
      (node (ref "J3") (pin "A9_B4") (pinfunction "VBUS_A9_B4") (pintype "power_in"))
      (node (ref "U$1") (pin "P$AD2") (pinfunction "VBUS_P$AD2") (pintype "power_in"))
    )
    (net (code "97") (name "VREG") (class "Default")
      (node (ref "C23") (pin "2") (pinfunction "2_2") (pintype "passive"))
      (node (ref "C24") (pin "2") (pinfunction "2_2") (pintype "passive"))
      (node (ref "C39") (pin "1") (pinfunction "1_1") (pintype "passive"))
      (node (ref "IC1") (pin "B2") (pinfunction "SYS_B2") (pintype "bidirectional"))
      (node (ref "IC2") (pin "A1") (pinfunction "EN_A1") (pintype "bidirectional"))
      (node (ref "IC2") (pin "A2") (pinfunction "VIN_1_A2") (pintype "bidirectional"))
      (node (ref "IC2") (pin "A3") (pinfunction "VIN_2_A3") (pintype "bidirectional"))
      (node (ref "TP2") (pin "TP") (pinfunction "TP_TP") (pintype "input"))
    )
    (net (code "98") (name "unconnected-(ANT1-NC-Pad2)") (class "Default")
      (node (ref "ANT1") (pin "2") (pinfunction "NC_2") (pintype "no_connect"))
    )
    (net (code "99") (name "unconnected-(IC3-ASCL-Pad11)") (class "Default")
      (node (ref "IC3") (pin "11") (pinfunction "ASCL_11") (pintype "bidirectional"))
    )
    (net (code "100") (name "unconnected-(IC3-ASDA-Pad4)") (class "Default")
      (node (ref "IC3") (pin "4") (pinfunction "ASDA_4") (pintype "bidirectional"))
    )
    (net (code "101") (name "unconnected-(J2-Pad1)") (class "Default")
      (node (ref "J2") (pin "1") (pinfunction "1_1") (pintype "bidirectional"))
    )
    (net (code "102") (name "unconnected-(J2-Pad6)") (class "Default")
      (node (ref "J2") (pin "6") (pinfunction "6_6") (pintype "bidirectional"))
    )
    (net (code "103") (name "unconnected-(J2-Pad7)") (class "Default")
      (node (ref "J2") (pin "7") (pinfunction "7_7") (pintype "bidirectional"))
    )
    (net (code "104") (name "unconnected-(J3-SBU1-PadA8)") (class "Default")
      (node (ref "J3") (pin "A8") (pinfunction "SBU1_A8") (pintype "bidirectional"))
    )
    (net (code "105") (name "unconnected-(J3-SBU2-PadB8)") (class "Default")
      (node (ref "J3") (pin "B8") (pinfunction "SBU2_B8") (pintype "bidirectional"))
    )
    (net (code "106") (name "unconnected-(U$1-DCCH-PadP$AB2)") (class "Default")
      (node (ref "U$1") (pin "P$AB2") (pinfunction "DCCH_P$AB2") (pintype "bidirectional"))
    )
  )
)
